# dash-hat.net
KiCad netlist of a schematic drawn in EAGLE
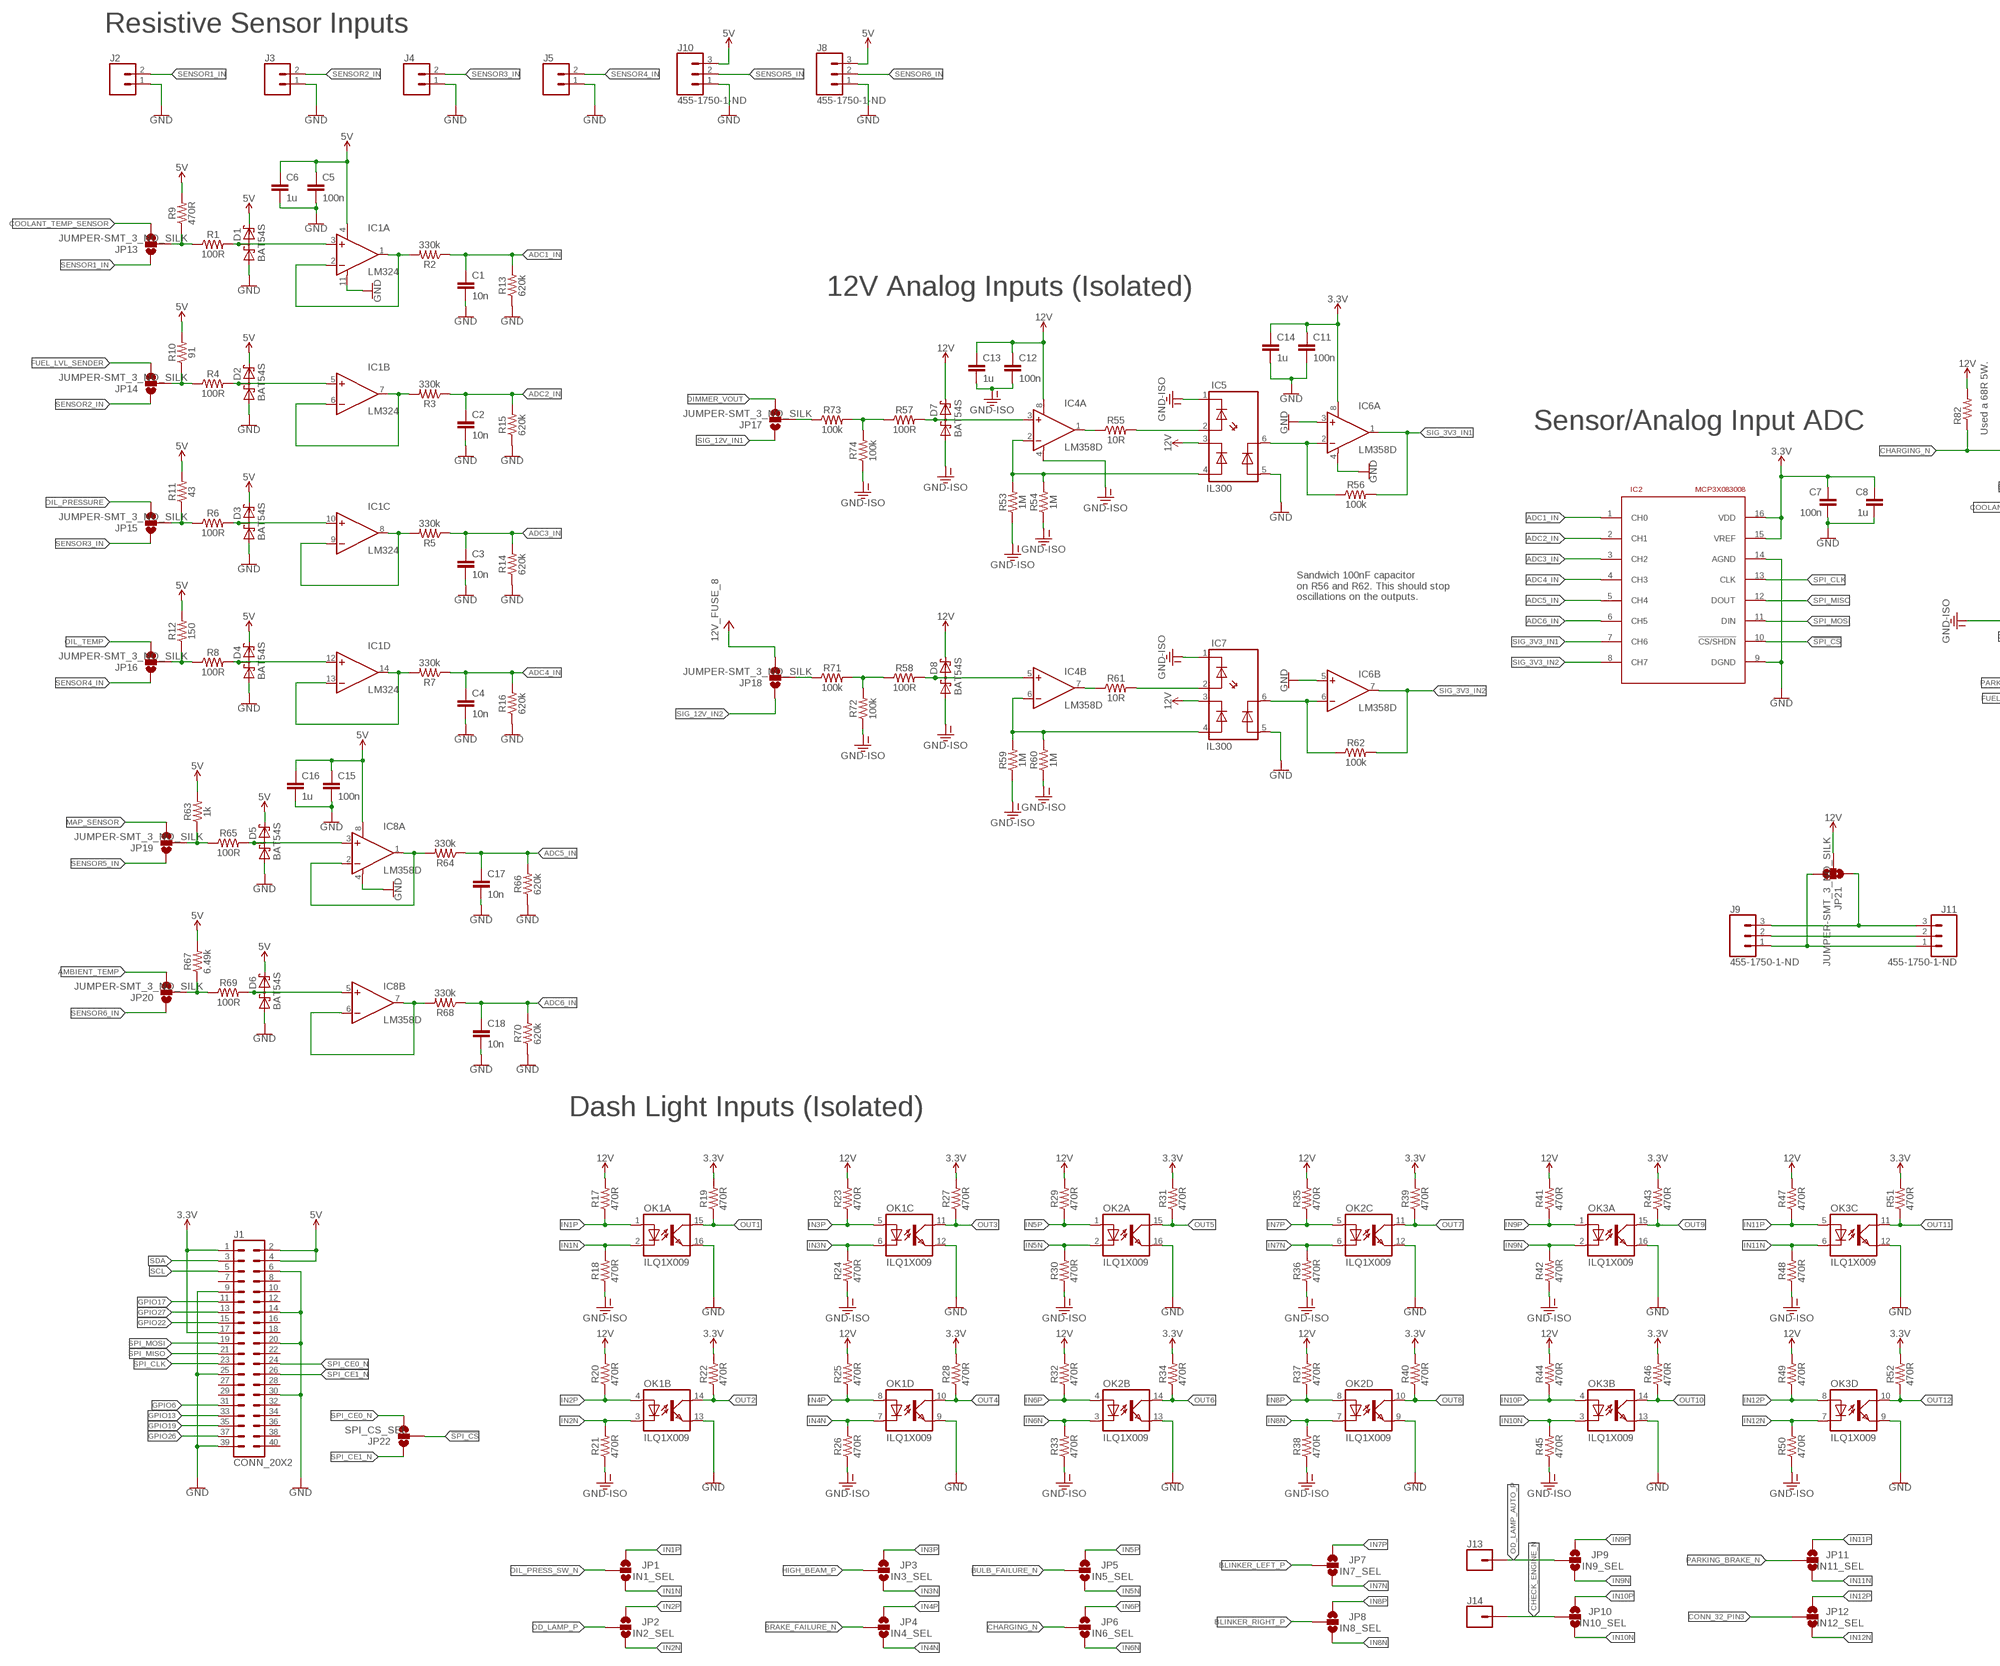
[diagram p0: schematic, sheet 1, part 1 of 2]
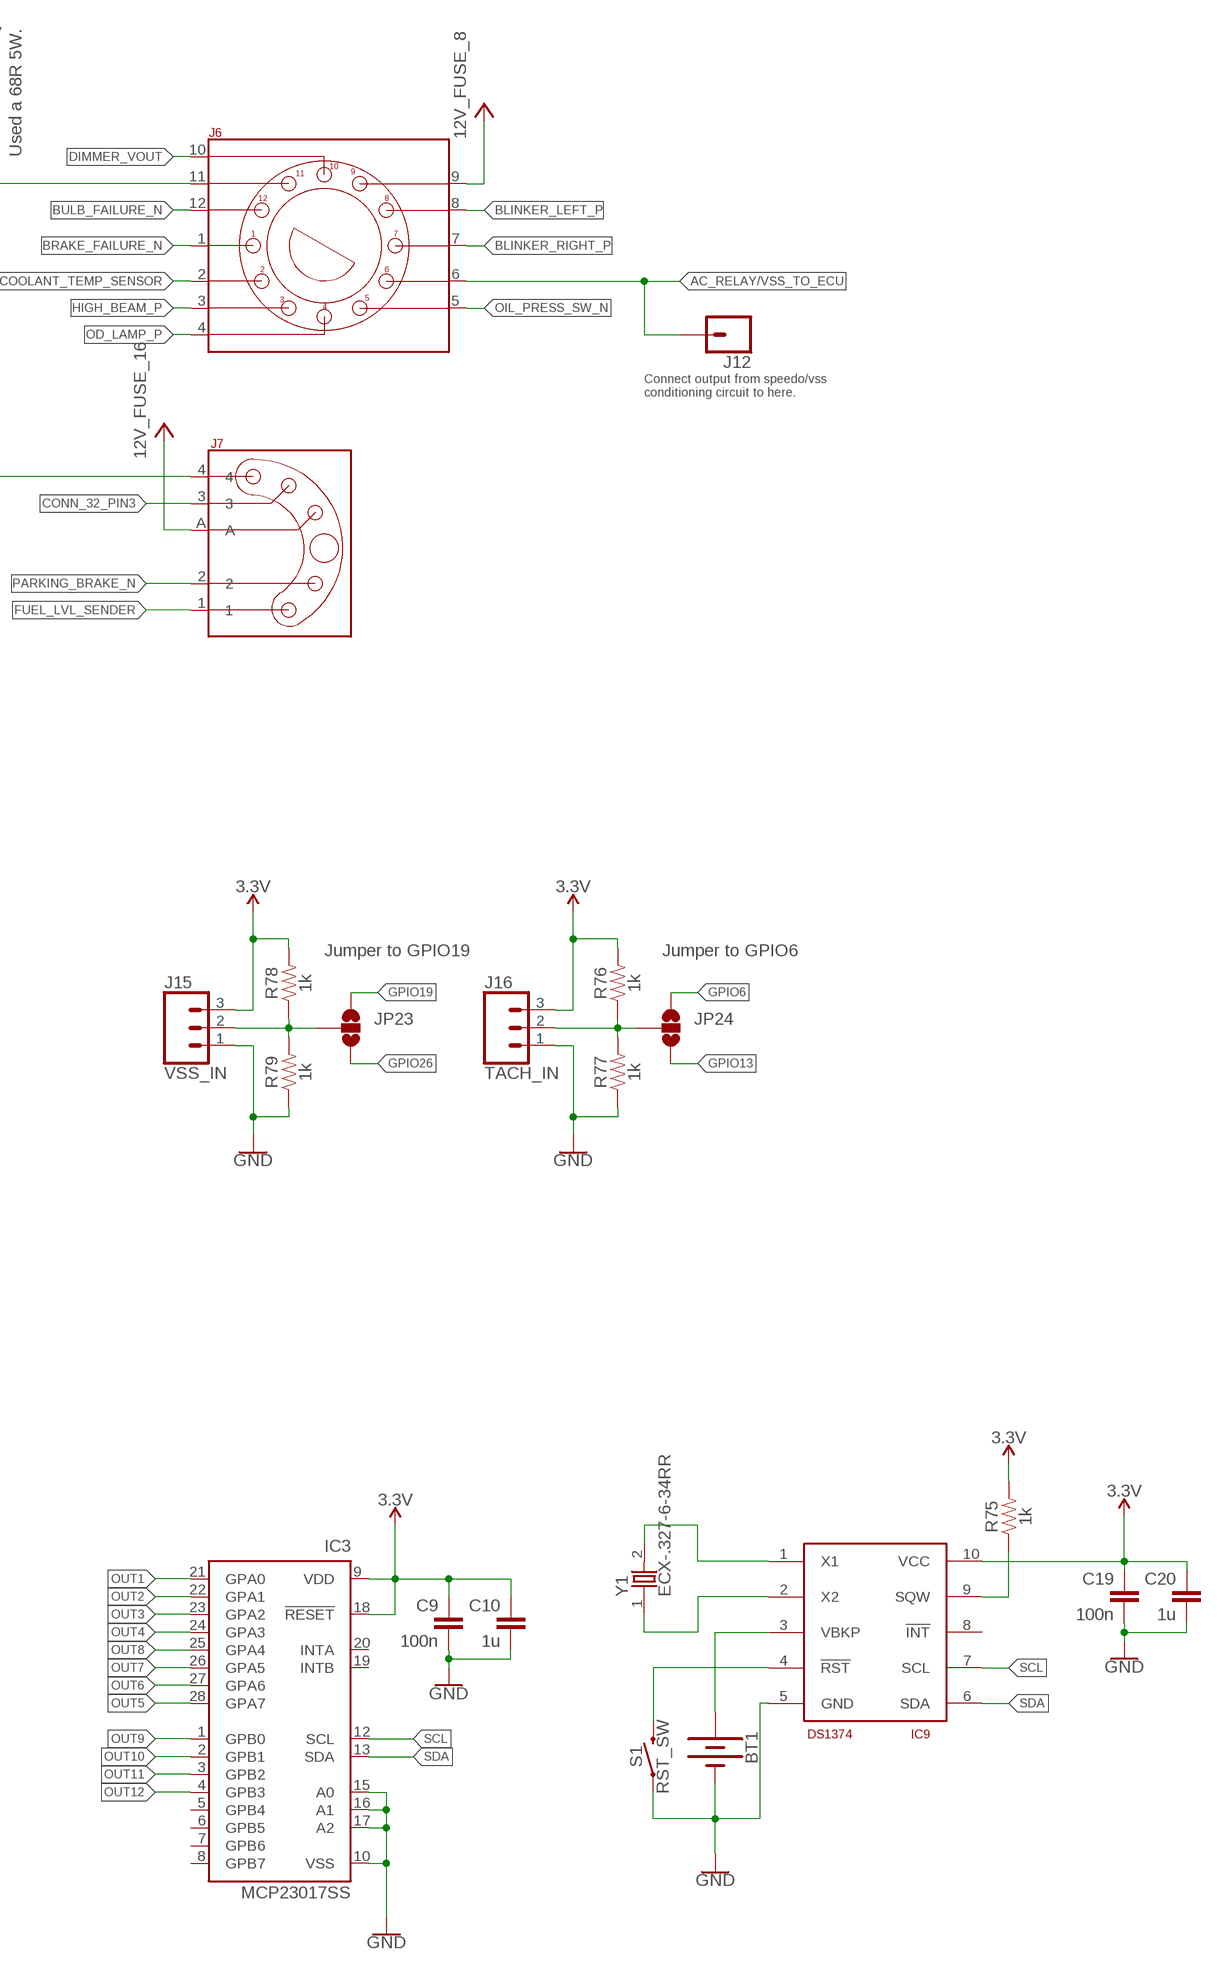
[diagram p1: schematic, sheet 1, part 2 of 2]

(export (version "E")
  (design (tool "Eeschema 10.0.6"))
  (components
    (comp (ref "BT1")
      (value "BATTERY-12MM_SMD")
      (footprint "eagle-import:BATTCON_12MM")
      (libsource (lib "eagle-import") (part "BATTERY-12MM_SMD"))
    )
    (comp (ref "C1")
      (value "10n")
      (footprint "eagle-import:0603")
      (libsource (lib "eagle-import") (part "CL10B103KB8NNNC"))
    )
    (comp (ref "C2")
      (value "10n")
      (footprint "eagle-import:0603")
      (libsource (lib "eagle-import") (part "CL10B103KB8NNNC"))
    )
    (comp (ref "C3")
      (value "10n")
      (footprint "eagle-import:0603")
      (libsource (lib "eagle-import") (part "CL10B103KB8NNNC"))
    )
    (comp (ref "C4")
      (value "10n")
      (footprint "eagle-import:0603")
      (libsource (lib "eagle-import") (part "CL10B103KB8NNNC"))
    )
    (comp (ref "C5")
      (value "100n")
      (footprint "eagle-import:0603")
      (libsource (lib "eagle-import") (part "CL10B104MB8NNNC"))
    )
    (comp (ref "C6")
      (value "1u")
      (footprint "eagle-import:0603")
      (libsource (lib "eagle-import") (part "CL10A105KA8NNNC"))
    )
    (comp (ref "C7")
      (value "100n")
      (footprint "eagle-import:0603")
      (libsource (lib "eagle-import") (part "CL10B104MB8NNNC"))
    )
    (comp (ref "C8")
      (value "1u")
      (footprint "eagle-import:0603")
      (libsource (lib "eagle-import") (part "CL10A105KA8NNNC"))
    )
    (comp (ref "C9")
      (value "100n")
      (footprint "eagle-import:0603")
      (libsource (lib "eagle-import") (part "CL10B104MB8NNNC"))
    )
    (comp (ref "C10")
      (value "1u")
      (footprint "eagle-import:0603")
      (libsource (lib "eagle-import") (part "CL10A105KA8NNNC"))
    )
    (comp (ref "C11")
      (value "100n")
      (footprint "eagle-import:0603")
      (libsource (lib "eagle-import") (part "CL10B104MB8NNNC"))
    )
    (comp (ref "C12")
      (value "100n")
      (footprint "eagle-import:0603")
      (libsource (lib "eagle-import") (part "CL10B104MB8NNNC"))
    )
    (comp (ref "C13")
      (value "1u")
      (footprint "eagle-import:0603")
      (libsource (lib "eagle-import") (part "CL10A105KA8NNNC"))
    )
    (comp (ref "C14")
      (value "1u")
      (footprint "eagle-import:0603")
      (libsource (lib "eagle-import") (part "CL10A105KA8NNNC"))
    )
    (comp (ref "C15")
      (value "100n")
      (footprint "eagle-import:0603")
      (libsource (lib "eagle-import") (part "CL10B104MB8NNNC"))
    )
    (comp (ref "C16")
      (value "1u")
      (footprint "eagle-import:0603")
      (libsource (lib "eagle-import") (part "CL10A105KA8NNNC"))
    )
    (comp (ref "C17")
      (value "10n")
      (footprint "eagle-import:0603")
      (libsource (lib "eagle-import") (part "CL10B103KB8NNNC"))
    )
    (comp (ref "C18")
      (value "10n")
      (footprint "eagle-import:0603")
      (libsource (lib "eagle-import") (part "CL10B103KB8NNNC"))
    )
    (comp (ref "C19")
      (value "100n")
      (footprint "eagle-import:0603")
      (libsource (lib "eagle-import") (part "CL10B104MB8NNNC"))
    )
    (comp (ref "C20")
      (value "1u")
      (footprint "eagle-import:0603")
      (libsource (lib "eagle-import") (part "CL10A105KA8NNNC"))
    )
    (comp (ref "D1")
      (value "BAT54S")
      (footprint "eagle-import:SOT23")
      (libsource (lib "eagle-import") (part "BAT54S"))
    )
    (comp (ref "D2")
      (value "BAT54S")
      (footprint "eagle-import:SOT23")
      (libsource (lib "eagle-import") (part "BAT54S"))
    )
    (comp (ref "D3")
      (value "BAT54S")
      (footprint "eagle-import:SOT23")
      (libsource (lib "eagle-import") (part "BAT54S"))
    )
    (comp (ref "D4")
      (value "BAT54S")
      (footprint "eagle-import:SOT23")
      (libsource (lib "eagle-import") (part "BAT54S"))
    )
    (comp (ref "D5")
      (value "BAT54S")
      (footprint "eagle-import:SOT23")
      (libsource (lib "eagle-import") (part "BAT54S"))
    )
    (comp (ref "D6")
      (value "BAT54S")
      (footprint "eagle-import:SOT23")
      (libsource (lib "eagle-import") (part "BAT54S"))
    )
    (comp (ref "D7")
      (value "BAT54S")
      (footprint "eagle-import:SOT23")
      (libsource (lib "eagle-import") (part "BAT54S"))
    )
    (comp (ref "D8")
      (value "BAT54S")
      (footprint "eagle-import:SOT23")
      (libsource (lib "eagle-import") (part "BAT54S"))
    )
    (comp (ref "IC1")
      (value "LM324")
      (footprint "eagle-import:TSSOP14")
      (libsource (lib "eagle-import") (part "LM324"))
    )
    (comp (ref "IC2")
      (value "MCP3X083008")
      (footprint "eagle-import:SO16")
      (libsource (lib "eagle-import") (part "MCP3X083008"))
    )
    (comp (ref "IC3")
      (value "MCP23017SS")
      (footprint "eagle-import:SSOP28")
      (fields (field (name "MF") "MICROCHIP") (field (name "MPN") "MCP23017-E/SS"))
      (libsource (lib "eagle-import") (part "MCP23017SS"))
    )
    (comp (ref "IC4")
      (value "LM358D")
      (footprint "eagle-import:SO08")
      (libsource (lib "eagle-import") (part "LM358D"))
    )
    (comp (ref "IC5")
      (value "IL300")
      (footprint "eagle-import:DIL8-SMD")
      (libsource (lib "eagle-import") (part "IL300"))
    )
    (comp (ref "IC6")
      (value "LM358D")
      (footprint "eagle-import:SO08")
      (libsource (lib "eagle-import") (part "LM358D"))
    )
    (comp (ref "IC7")
      (value "IL300")
      (footprint "eagle-import:DIL8-SMD")
      (libsource (lib "eagle-import") (part "IL300"))
    )
    (comp (ref "IC8")
      (value "LM358D")
      (footprint "eagle-import:SO08")
      (libsource (lib "eagle-import") (part "LM358D"))
    )
    (comp (ref "IC9")
      (value "DS1374")
      (footprint "eagle-import:UMAX10")
      (libsource (lib "eagle-import") (part "DS1374"))
    )
    (comp (ref "J1")
      (value "CONN_20X2")
      (footprint "eagle-import:2X20")
      (libsource (lib "eagle-import") (part "CONN_20X2"))
    )
    (comp (ref "J2")
      (value "CONN_02")
      (footprint "eagle-import:1X02")
      (libsource (lib "eagle-import") (part "CONN_02"))
    )
    (comp (ref "J3")
      (value "CONN_02")
      (footprint "eagle-import:1X02")
      (libsource (lib "eagle-import") (part "CONN_02"))
    )
    (comp (ref "J4")
      (value "CONN_02")
      (footprint "eagle-import:1X02")
      (libsource (lib "eagle-import") (part "CONN_02"))
    )
    (comp (ref "J5")
      (value "CONN_02")
      (footprint "eagle-import:1X02")
      (libsource (lib "eagle-import") (part "CONN_02"))
    )
    (comp (ref "J6")
      (value "VOLVO_CONN_31")
      (footprint "eagle-import:VOLVO_CON_31")
      (libsource (lib "eagle-import") (part "VOLVO_CONN_31"))
    )
    (comp (ref "J7")
      (value "VOLVO_CONN_32")
      (footprint "eagle-import:VOLVO_CON_32")
      (libsource (lib "eagle-import") (part "VOLVO_CONN_32"))
    )
    (comp (ref "J8")
      (value "455-1750-1-ND")
      (footprint "eagle-import:1X03")
      (libsource (lib "eagle-import") (part "CONN_03"))
    )
    (comp (ref "J9")
      (value "455-1750-1-ND")
      (footprint "eagle-import:1X03")
      (libsource (lib "eagle-import") (part "CONN_03"))
    )
    (comp (ref "J10")
      (value "455-1750-1-ND")
      (footprint "eagle-import:1X03")
      (libsource (lib "eagle-import") (part "CONN_03"))
    )
    (comp (ref "J11")
      (value "455-1750-1-ND")
      (footprint "eagle-import:1X03")
      (libsource (lib "eagle-import") (part "CONN_03"))
    )
    (comp (ref "J12")
      (value "CONN_01OFFSET")
      (footprint "eagle-import:1X01_OFFSET")
      (libsource (lib "eagle-import") (part "CONN_01OFFSET"))
    )
    (comp (ref "J13")
      (value "CONN_01PTH_2MM")
      (footprint "eagle-import:1X01_2MM")
      (libsource (lib "eagle-import") (part "CONN_01PTH_2MM"))
    )
    (comp (ref "J14")
      (value "CONN_01PTH_2MM")
      (footprint "eagle-import:1X01_2MM")
      (libsource (lib "eagle-import") (part "CONN_01PTH_2MM"))
    )
    (comp (ref "J15")
      (value "VSS_IN")
      (footprint "eagle-import:1X03")
      (libsource (lib "eagle-import") (part "CONN_03"))
    )
    (comp (ref "J16")
      (value "TACH_IN")
      (footprint "eagle-import:1X03")
      (libsource (lib "eagle-import") (part "CONN_03"))
    )
    (comp (ref "JP1")
      (value "IN1_SEL")
      (footprint "eagle-import:SMT-JUMPER_3_NO_SILK")
      (libsource (lib "eagle-import") (part "JUMPER-SMT_3_NO_SILK"))
    )
    (comp (ref "JP2")
      (value "IN2_SEL")
      (footprint "eagle-import:SMT-JUMPER_3_NO_SILK")
      (libsource (lib "eagle-import") (part "JUMPER-SMT_3_NO_SILK"))
    )
    (comp (ref "JP3")
      (value "IN3_SEL")
      (footprint "eagle-import:SMT-JUMPER_3_NO_SILK")
      (libsource (lib "eagle-import") (part "JUMPER-SMT_3_NO_SILK"))
    )
    (comp (ref "JP4")
      (value "IN4_SEL")
      (footprint "eagle-import:SMT-JUMPER_3_NO_SILK")
      (libsource (lib "eagle-import") (part "JUMPER-SMT_3_NO_SILK"))
    )
    (comp (ref "JP5")
      (value "IN5_SEL")
      (footprint "eagle-import:SMT-JUMPER_3_NO_SILK")
      (libsource (lib "eagle-import") (part "JUMPER-SMT_3_NO_SILK"))
    )
    (comp (ref "JP6")
      (value "IN6_SEL")
      (footprint "eagle-import:SMT-JUMPER_3_NO_SILK")
      (libsource (lib "eagle-import") (part "JUMPER-SMT_3_NO_SILK"))
    )
    (comp (ref "JP7")
      (value "IN7_SEL")
      (footprint "eagle-import:SMT-JUMPER_3_NO_SILK")
      (libsource (lib "eagle-import") (part "JUMPER-SMT_3_NO_SILK"))
    )
    (comp (ref "JP8")
      (value "IN8_SEL")
      (footprint "eagle-import:SMT-JUMPER_3_NO_SILK")
      (libsource (lib "eagle-import") (part "JUMPER-SMT_3_NO_SILK"))
    )
    (comp (ref "JP9")
      (value "IN9_SEL")
      (footprint "eagle-import:SMT-JUMPER_3_NO_SILK")
      (libsource (lib "eagle-import") (part "JUMPER-SMT_3_NO_SILK"))
    )
    (comp (ref "JP10")
      (value "IN10_SEL")
      (footprint "eagle-import:SMT-JUMPER_3_NO_SILK")
      (libsource (lib "eagle-import") (part "JUMPER-SMT_3_NO_SILK"))
    )
    (comp (ref "JP11")
      (value "IN11_SEL")
      (footprint "eagle-import:SMT-JUMPER_3_NO_SILK")
      (libsource (lib "eagle-import") (part "JUMPER-SMT_3_NO_SILK"))
    )
    (comp (ref "JP12")
      (value "IN12_SEL")
      (footprint "eagle-import:SMT-JUMPER_3_NO_SILK")
      (libsource (lib "eagle-import") (part "JUMPER-SMT_3_NO_SILK"))
    )
    (comp (ref "JP13")
      (value "JUMPER-SMT_3_NO_SILK")
      (footprint "eagle-import:SMT-JUMPER_3_NO_SILK")
      (libsource (lib "eagle-import") (part "JUMPER-SMT_3_NO_SILK"))
    )
    (comp (ref "JP14")
      (value "JUMPER-SMT_3_NO_SILK")
      (footprint "eagle-import:SMT-JUMPER_3_NO_SILK")
      (libsource (lib "eagle-import") (part "JUMPER-SMT_3_NO_SILK"))
    )
    (comp (ref "JP15")
      (value "JUMPER-SMT_3_NO_SILK")
      (footprint "eagle-import:SMT-JUMPER_3_NO_SILK")
      (libsource (lib "eagle-import") (part "JUMPER-SMT_3_NO_SILK"))
    )
    (comp (ref "JP16")
      (value "JUMPER-SMT_3_NO_SILK")
      (footprint "eagle-import:SMT-JUMPER_3_NO_SILK")
      (libsource (lib "eagle-import") (part "JUMPER-SMT_3_NO_SILK"))
    )
    (comp (ref "JP17")
      (value "JUMPER-SMT_3_NO_SILK")
      (footprint "eagle-import:SMT-JUMPER_3_NO_SILK")
      (libsource (lib "eagle-import") (part "JUMPER-SMT_3_NO_SILK"))
    )
    (comp (ref "JP18")
      (value "JUMPER-SMT_3_NO_SILK")
      (footprint "eagle-import:SMT-JUMPER_3_NO_SILK")
      (libsource (lib "eagle-import") (part "JUMPER-SMT_3_NO_SILK"))
    )
    (comp (ref "JP19")
      (value "JUMPER-SMT_3_NO_SILK")
      (footprint "eagle-import:SMT-JUMPER_3_NO_SILK")
      (libsource (lib "eagle-import") (part "JUMPER-SMT_3_NO_SILK"))
    )
    (comp (ref "JP20")
      (value "JUMPER-SMT_3_NO_SILK")
      (footprint "eagle-import:SMT-JUMPER_3_NO_SILK")
      (libsource (lib "eagle-import") (part "JUMPER-SMT_3_NO_SILK"))
    )
    (comp (ref "JP21")
      (value "JUMPER-SMT_3_NO_SILK")
      (footprint "eagle-import:SMT-JUMPER_3_NO_SILK")
      (libsource (lib "eagle-import") (part "JUMPER-SMT_3_NO_SILK"))
    )
    (comp (ref "JP22")
      (value "SPI_CS_SEL")
      (footprint "eagle-import:SMT-JUMPER_3_NO_SILK")
      (libsource (lib "eagle-import") (part "JUMPER-SMT_3_NO_SILK"))
    )
    (comp (ref "JP23")
      (value "TACH_INPUT_SEL")
      (footprint "eagle-import:SMT-JUMPER_3_NO_SILK")
      (libsource (lib "eagle-import") (part "JUMPER-SMT_3_NO_SILK"))
    )
    (comp (ref "JP24")
      (value "TACH_INPUT_SEL")
      (footprint "eagle-import:SMT-JUMPER_3_NO_SILK")
      (libsource (lib "eagle-import") (part "JUMPER-SMT_3_NO_SILK"))
    )
    (comp (ref "OK1")
      (value "ILQ1X009")
      (footprint "eagle-import:SMD16")
      (libsource (lib "eagle-import") (part "ILQ1X009"))
    )
    (comp (ref "OK2")
      (value "ILQ1X009")
      (footprint "eagle-import:SMD16")
      (libsource (lib "eagle-import") (part "ILQ1X009"))
    )
    (comp (ref "OK3")
      (value "ILQ1X009")
      (footprint "eagle-import:SMD16")
      (libsource (lib "eagle-import") (part "ILQ1X009"))
    )
    (comp (ref "R1")
      (value "100R")
      (footprint "eagle-import:0603")
      (libsource (lib "eagle-import") (part "RC0603JR-07100RL"))
    )
    (comp (ref "R2")
      (value "330k")
      (footprint "eagle-import:0603")
      (libsource (lib "eagle-import") (part "RC0603JR-07330KL"))
    )
    (comp (ref "R3")
      (value "330k")
      (footprint "eagle-import:0603")
      (libsource (lib "eagle-import") (part "RC0603JR-07330KL"))
    )
    (comp (ref "R4")
      (value "100R")
      (footprint "eagle-import:0603")
      (libsource (lib "eagle-import") (part "RC0603JR-07100RL"))
    )
    (comp (ref "R5")
      (value "330k")
      (footprint "eagle-import:0603")
      (libsource (lib "eagle-import") (part "RC0603JR-07330KL"))
    )
    (comp (ref "R6")
      (value "100R")
      (footprint "eagle-import:0603")
      (libsource (lib "eagle-import") (part "RC0603JR-07100RL"))
    )
    (comp (ref "R7")
      (value "330k")
      (footprint "eagle-import:0603")
      (libsource (lib "eagle-import") (part "RC0603JR-07330KL"))
    )
    (comp (ref "R8")
      (value "100R")
      (footprint "eagle-import:0603")
      (libsource (lib "eagle-import") (part "RC0603JR-07100RL"))
    )
    (comp (ref "R9")
      (value "470R")
      (footprint "eagle-import:0603")
      (libsource (lib "eagle-import") (part "RC0603JR-07470RL"))
    )
    (comp (ref "R10")
      (value "91")
      (footprint "eagle-import:0603")
      (libsource (lib "eagle-import") (part "RC0603JR-071KL"))
    )
    (comp (ref "R11")
      (value "43")
      (footprint "eagle-import:0603")
      (libsource (lib "eagle-import") (part "RC0603JR-071KL"))
    )
    (comp (ref "R12")
      (value "150")
      (footprint "eagle-import:0603")
      (libsource (lib "eagle-import") (part "RC0603JR-071KL"))
    )
    (comp (ref "R13")
      (value "620k")
      (footprint "eagle-import:0603")
      (libsource (lib "eagle-import") (part "RC0603JR-07620KL"))
    )
    (comp (ref "R14")
      (value "620k")
      (footprint "eagle-import:0603")
      (libsource (lib "eagle-import") (part "RC0603JR-07620KL"))
    )
    (comp (ref "R15")
      (value "620k")
      (footprint "eagle-import:0603")
      (libsource (lib "eagle-import") (part "RC0603JR-07620KL"))
    )
    (comp (ref "R16")
      (value "620k")
      (footprint "eagle-import:0603")
      (libsource (lib "eagle-import") (part "RC0603JR-07620KL"))
    )
    (comp (ref "R17")
      (value "470R")
      (footprint "eagle-import:0603")
      (libsource (lib "eagle-import") (part "RC0603JR-07470RL"))
    )
    (comp (ref "R18")
      (value "470R")
      (footprint "eagle-import:0603")
      (libsource (lib "eagle-import") (part "RC0603JR-07470RL"))
    )
    (comp (ref "R19")
      (value "470R")
      (footprint "eagle-import:0603")
      (libsource (lib "eagle-import") (part "RC0603JR-07470RL"))
    )
    (comp (ref "R20")
      (value "470R")
      (footprint "eagle-import:0603")
      (libsource (lib "eagle-import") (part "RC0603JR-07470RL"))
    )
    (comp (ref "R21")
      (value "470R")
      (footprint "eagle-import:0603")
      (libsource (lib "eagle-import") (part "RC0603JR-07470RL"))
    )
    (comp (ref "R22")
      (value "470R")
      (footprint "eagle-import:0603")
      (libsource (lib "eagle-import") (part "RC0603JR-07470RL"))
    )
    (comp (ref "R23")
      (value "470R")
      (footprint "eagle-import:0603")
      (libsource (lib "eagle-import") (part "RC0603JR-07470RL"))
    )
    (comp (ref "R24")
      (value "470R")
      (footprint "eagle-import:0603")
      (libsource (lib "eagle-import") (part "RC0603JR-07470RL"))
    )
    (comp (ref "R25")
      (value "470R")
      (footprint "eagle-import:0603")
      (libsource (lib "eagle-import") (part "RC0603JR-07470RL"))
    )
    (comp (ref "R26")
      (value "470R")
      (footprint "eagle-import:0603")
      (libsource (lib "eagle-import") (part "RC0603JR-07470RL"))
    )
    (comp (ref "R27")
      (value "470R")
      (footprint "eagle-import:0603")
      (libsource (lib "eagle-import") (part "RC0603JR-07470RL"))
    )
    (comp (ref "R28")
      (value "470R")
      (footprint "eagle-import:0603")
      (libsource (lib "eagle-import") (part "RC0603JR-07470RL"))
    )
    (comp (ref "R29")
      (value "470R")
      (footprint "eagle-import:0603")
      (libsource (lib "eagle-import") (part "RC0603JR-07470RL"))
    )
    (comp (ref "R30")
      (value "470R")
      (footprint "eagle-import:0603")
      (libsource (lib "eagle-import") (part "RC0603JR-07470RL"))
    )
    (comp (ref "R31")
      (value "470R")
      (footprint "eagle-import:0603")
      (libsource (lib "eagle-import") (part "RC0603JR-07470RL"))
    )
    (comp (ref "R32")
      (value "470R")
      (footprint "eagle-import:0603")
      (libsource (lib "eagle-import") (part "RC0603JR-07470RL"))
    )
    (comp (ref "R33")
      (value "470R")
      (footprint "eagle-import:0603")
      (libsource (lib "eagle-import") (part "RC0603JR-07470RL"))
    )
    (comp (ref "R34")
      (value "470R")
      (footprint "eagle-import:0603")
      (libsource (lib "eagle-import") (part "RC0603JR-07470RL"))
    )
    (comp (ref "R35")
      (value "470R")
      (footprint "eagle-import:0603")
      (libsource (lib "eagle-import") (part "RC0603JR-07470RL"))
    )
    (comp (ref "R36")
      (value "470R")
      (footprint "eagle-import:0603")
      (libsource (lib "eagle-import") (part "RC0603JR-07470RL"))
    )
    (comp (ref "R37")
      (value "470R")
      (footprint "eagle-import:0603")
      (libsource (lib "eagle-import") (part "RC0603JR-07470RL"))
    )
    (comp (ref "R38")
      (value "470R")
      (footprint "eagle-import:0603")
      (libsource (lib "eagle-import") (part "RC0603JR-07470RL"))
    )
    (comp (ref "R39")
      (value "470R")
      (footprint "eagle-import:0603")
      (libsource (lib "eagle-import") (part "RC0603JR-07470RL"))
    )
    (comp (ref "R40")
      (value "470R")
      (footprint "eagle-import:0603")
      (libsource (lib "eagle-import") (part "RC0603JR-07470RL"))
    )
    (comp (ref "R41")
      (value "470R")
      (footprint "eagle-import:0603")
      (libsource (lib "eagle-import") (part "RC0603JR-07470RL"))
    )
    (comp (ref "R42")
      (value "470R")
      (footprint "eagle-import:0603")
      (libsource (lib "eagle-import") (part "RC0603JR-07470RL"))
    )
    (comp (ref "R43")
      (value "470R")
      (footprint "eagle-import:0603")
      (libsource (lib "eagle-import") (part "RC0603JR-07470RL"))
    )
    (comp (ref "R44")
      (value "470R")
      (footprint "eagle-import:0603")
      (libsource (lib "eagle-import") (part "RC0603JR-07470RL"))
    )
    (comp (ref "R45")
      (value "470R")
      (footprint "eagle-import:0603")
      (libsource (lib "eagle-import") (part "RC0603JR-07470RL"))
    )
    (comp (ref "R46")
      (value "470R")
      (footprint "eagle-import:0603")
      (libsource (lib "eagle-import") (part "RC0603JR-07470RL"))
    )
    (comp (ref "R47")
      (value "470R")
      (footprint "eagle-import:0603")
      (libsource (lib "eagle-import") (part "RC0603JR-07470RL"))
    )
    (comp (ref "R48")
      (value "470R")
      (footprint "eagle-import:0603")
      (libsource (lib "eagle-import") (part "RC0603JR-07470RL"))
    )
    (comp (ref "R49")
      (value "470R")
      (footprint "eagle-import:0603")
      (libsource (lib "eagle-import") (part "RC0603JR-07470RL"))
    )
    (comp (ref "R50")
      (value "470R")
      (footprint "eagle-import:0603")
      (libsource (lib "eagle-import") (part "RC0603JR-07470RL"))
    )
    (comp (ref "R51")
      (value "470R")
      (footprint "eagle-import:0603")
      (libsource (lib "eagle-import") (part "RC0603JR-07470RL"))
    )
    (comp (ref "R52")
      (value "470R")
      (footprint "eagle-import:0603")
      (libsource (lib "eagle-import") (part "RC0603JR-07470RL"))
    )
    (comp (ref "R53")
      (value "1M")
      (footprint "eagle-import:0603")
      (libsource (lib "eagle-import") (part "RC0603JR-071ML"))
    )
    (comp (ref "R54")
      (value "1M")
      (footprint "eagle-import:0603")
      (libsource (lib "eagle-import") (part "RC0603JR-071ML"))
    )
    (comp (ref "R55")
      (value "10R")
      (footprint "eagle-import:0603")
      (libsource (lib "eagle-import") (part "RC0603JR-1310RL"))
    )
    (comp (ref "R56")
      (value "100k")
      (footprint "eagle-import:0603")
      (libsource (lib "eagle-import") (part "RC0603JR-07100KL"))
    )
    (comp (ref "R57")
      (value "100R")
      (footprint "eagle-import:0603")
      (libsource (lib "eagle-import") (part "RC0603JR-07100RL"))
    )
    (comp (ref "R58")
      (value "100R")
      (footprint "eagle-import:0603")
      (libsource (lib "eagle-import") (part "RC0603JR-07100RL"))
    )
    (comp (ref "R59")
      (value "1M")
      (footprint "eagle-import:0603")
      (libsource (lib "eagle-import") (part "RC0603JR-071ML"))
    )
    (comp (ref "R60")
      (value "1M")
      (footprint "eagle-import:0603")
      (libsource (lib "eagle-import") (part "RC0603JR-071ML"))
    )
    (comp (ref "R61")
      (value "10R")
      (footprint "eagle-import:0603")
      (libsource (lib "eagle-import") (part "RC0603JR-1310RL"))
    )
    (comp (ref "R62")
      (value "100k")
      (footprint "eagle-import:0603")
      (libsource (lib "eagle-import") (part "RC0603JR-07100KL"))
    )
    (comp (ref "R63")
      (value "1k")
      (footprint "eagle-import:0603")
      (libsource (lib "eagle-import") (part "RC0603JR-071KL"))
    )
    (comp (ref "R64")
      (value "330k")
      (footprint "eagle-import:0603")
      (libsource (lib "eagle-import") (part "RC0603JR-07330KL"))
    )
    (comp (ref "R65")
      (value "100R")
      (footprint "eagle-import:0603")
      (libsource (lib "eagle-import") (part "RC0603JR-07100RL"))
    )
    (comp (ref "R66")
      (value "620k")
      (footprint "eagle-import:0603")
      (libsource (lib "eagle-import") (part "RC0603JR-07620KL"))
    )
    (comp (ref "R67")
      (value "6.49k")
      (footprint "eagle-import:0603")
      (libsource (lib "eagle-import") (part "RC0603JR-071KL"))
    )
    (comp (ref "R68")
      (value "330k")
      (footprint "eagle-import:0603")
      (libsource (lib "eagle-import") (part "RC0603JR-07330KL"))
    )
    (comp (ref "R69")
      (value "100R")
      (footprint "eagle-import:0603")
      (libsource (lib "eagle-import") (part "RC0603JR-07100RL"))
    )
    (comp (ref "R70")
      (value "620k")
      (footprint "eagle-import:0603")
      (libsource (lib "eagle-import") (part "RC0603JR-07620KL"))
    )
    (comp (ref "R71")
      (value "100k")
      (footprint "eagle-import:0603")
      (libsource (lib "eagle-import") (part "RC0603JR-07100KL"))
    )
    (comp (ref "R72")
      (value "100k")
      (footprint "eagle-import:0603")
      (libsource (lib "eagle-import") (part "RC0603JR-07100KL"))
    )
    (comp (ref "R73")
      (value "100k")
      (footprint "eagle-import:0603")
      (libsource (lib "eagle-import") (part "RC0603JR-07100KL"))
    )
    (comp (ref "R74")
      (value "100k")
      (footprint "eagle-import:0603")
      (libsource (lib "eagle-import") (part "RC0603JR-07100KL"))
    )
    (comp (ref "R75")
      (value "1k")
      (footprint "eagle-import:0603")
      (libsource (lib "eagle-import") (part "RC0603JR-071KL"))
    )
    (comp (ref "R76")
      (value "1k")
      (footprint "eagle-import:0603")
      (libsource (lib "eagle-import") (part "RC0603JR-071KL"))
    )
    (comp (ref "R77")
      (value "1k")
      (footprint "eagle-import:0603")
      (libsource (lib "eagle-import") (part "RC0603JR-071KL"))
    )
    (comp (ref "R78")
      (value "1k")
      (footprint "eagle-import:0603")
      (libsource (lib "eagle-import") (part "RC0603JR-071KL"))
    )
    (comp (ref "R79")
      (value "1k")
      (footprint "eagle-import:0603")
      (libsource (lib "eagle-import") (part "RC0603JR-071KL"))
    )
    (comp (ref "R82")
      (value "R-US_0617/17")
      (footprint "eagle-import:0617_17")
      (libsource (lib "eagle-import") (part "R-US_0617/17"))
    )
    (comp (ref "S1")
      (value "RST_SW")
      (footprint "eagle-import:TACTILE_SWITCH_SMD_6.0X3.5MM")
      (libsource (lib "eagle-import") (part "MOMENTARY-SWITCH-SPST-SMD-6.0X3.5MM"))
    )
    (comp (ref "Y1")
      (value "ECX-.327-6-34RR")
      (footprint "eagle-import:ECX-34RR")
      (libsource (lib "eagle-import") (part "ECX-.327-6-34RR"))
    )
  )
  (nets
    (net (code "1") (name "/~{SPI_CS}") (class "Default")
      (node (ref "IC2") (pin "10") (pinfunction "~{CS/SHDN}_10") (pintype "bidirectional"))
      (node (ref "JP22") (pin "2") (pinfunction "2_2") (pintype "passive"))
    )
    (net (code "2") (name "3.3V") (class "Default")
      (node (ref "C10") (pin "1") (pinfunction "1_1") (pintype "passive"))
      (node (ref "C11") (pin "1") (pinfunction "1_1") (pintype "passive"))
      (node (ref "C14") (pin "1") (pinfunction "1_1") (pintype "passive"))
      (node (ref "C19") (pin "1") (pinfunction "1_1") (pintype "passive"))
      (node (ref "C20") (pin "1") (pinfunction "1_1") (pintype "passive"))
      (node (ref "C7") (pin "1") (pinfunction "1_1") (pintype "passive"))
      (node (ref "C8") (pin "1") (pinfunction "1_1") (pintype "passive"))
      (node (ref "C9") (pin "1") (pinfunction "1_1") (pintype "passive"))
      (node (ref "IC2") (pin "15") (pinfunction "VREF_15") (pintype "bidirectional"))
      (node (ref "IC2") (pin "16") (pinfunction "VDD_16") (pintype "bidirectional"))
      (node (ref "IC3") (pin "18") (pinfunction "~{RESET}_18") (pintype "input"))
      (node (ref "IC3") (pin "9") (pinfunction "VDD_9") (pintype "power_in"))
      (node (ref "IC6") (pin "8") (pinfunction "V+_8") (pintype "power_in"))
      (node (ref "IC9") (pin "10") (pinfunction "VCC_10") (pintype "power_in"))
      (node (ref "J1") (pin "1") (pinfunction "1_1") (pintype "passive"))
      (node (ref "J1") (pin "17") (pinfunction "17_17") (pintype "passive"))
      (node (ref "J15") (pin "3") (pinfunction "3_3") (pintype "passive"))
      (node (ref "J16") (pin "3") (pinfunction "3_3") (pintype "passive"))
      (node (ref "R19") (pin "2") (pinfunction "2_2") (pintype "passive"))
      (node (ref "R22") (pin "2") (pinfunction "2_2") (pintype "passive"))
      (node (ref "R27") (pin "2") (pinfunction "2_2") (pintype "passive"))
      (node (ref "R28") (pin "2") (pinfunction "2_2") (pintype "passive"))
      (node (ref "R31") (pin "2") (pinfunction "2_2") (pintype "passive"))
      (node (ref "R34") (pin "2") (pinfunction "2_2") (pintype "passive"))
      (node (ref "R39") (pin "2") (pinfunction "2_2") (pintype "passive"))
      (node (ref "R40") (pin "2") (pinfunction "2_2") (pintype "passive"))
      (node (ref "R43") (pin "2") (pinfunction "2_2") (pintype "passive"))
      (node (ref "R46") (pin "2") (pinfunction "2_2") (pintype "passive"))
      (node (ref "R51") (pin "2") (pinfunction "2_2") (pintype "passive"))
      (node (ref "R52") (pin "2") (pinfunction "2_2") (pintype "passive"))
      (node (ref "R75") (pin "2") (pinfunction "2_2") (pintype "passive"))
      (node (ref "R76") (pin "2") (pinfunction "2_2") (pintype "passive"))
      (node (ref "R78") (pin "2") (pinfunction "2_2") (pintype "passive"))
    )
    (net (code "3") (name "5V") (class "Default")
      (node (ref "C15") (pin "1") (pinfunction "1_1") (pintype "passive"))
      (node (ref "C16") (pin "1") (pinfunction "1_1") (pintype "passive"))
      (node (ref "C5") (pin "1") (pinfunction "1_1") (pintype "passive"))
      (node (ref "C6") (pin "1") (pinfunction "1_1") (pintype "passive"))
      (node (ref "D1") (pin "2") (pinfunction "C2_2") (pintype "passive"))
      (node (ref "D2") (pin "2") (pinfunction "C2_2") (pintype "passive"))
      (node (ref "D3") (pin "2") (pinfunction "C2_2") (pintype "passive"))
      (node (ref "D4") (pin "2") (pinfunction "C2_2") (pintype "passive"))
      (node (ref "D5") (pin "2") (pinfunction "C2_2") (pintype "passive"))
      (node (ref "D6") (pin "2") (pinfunction "C2_2") (pintype "passive"))
      (node (ref "IC1") (pin "4") (pinfunction "V+_4") (pintype "power_in"))
      (node (ref "IC8") (pin "8") (pinfunction "V+_8") (pintype "power_in"))
      (node (ref "J1") (pin "2") (pinfunction "2_2") (pintype "passive"))
      (node (ref "J1") (pin "4") (pinfunction "4_4") (pintype "passive"))
      (node (ref "J10") (pin "3") (pinfunction "3_3") (pintype "passive"))
      (node (ref "J8") (pin "3") (pinfunction "3_3") (pintype "passive"))
      (node (ref "R10") (pin "2") (pinfunction "2_2") (pintype "passive"))
      (node (ref "R11") (pin "2") (pinfunction "2_2") (pintype "passive"))
      (node (ref "R12") (pin "2") (pinfunction "2_2") (pintype "passive"))
      (node (ref "R63") (pin "2") (pinfunction "2_2") (pintype "passive"))
      (node (ref "R67") (pin "2") (pinfunction "2_2") (pintype "passive"))
      (node (ref "R9") (pin "2") (pinfunction "2_2") (pintype "passive"))
    )
    (net (code "4") (name "12V") (class "Default")
      (node (ref "C12") (pin "1") (pinfunction "1_1") (pintype "passive"))
      (node (ref "C13") (pin "1") (pinfunction "1_1") (pintype "passive"))
      (node (ref "D7") (pin "2") (pinfunction "C2_2") (pintype "passive"))
      (node (ref "D8") (pin "2") (pinfunction "C2_2") (pintype "passive"))
      (node (ref "IC4") (pin "8") (pinfunction "V+_8") (pintype "power_in"))
      (node (ref "IC5") (pin "3") (pinfunction "C3_3") (pintype "passive"))
      (node (ref "IC7") (pin "3") (pinfunction "C3_3") (pintype "passive"))
      (node (ref "JP21") (pin "2") (pinfunction "2_2") (pintype "passive"))
      (node (ref "R17") (pin "2") (pinfunction "2_2") (pintype "passive"))
      (node (ref "R20") (pin "2") (pinfunction "2_2") (pintype "passive"))
      (node (ref "R23") (pin "2") (pinfunction "2_2") (pintype "passive"))
      (node (ref "R25") (pin "2") (pinfunction "2_2") (pintype "passive"))
      (node (ref "R29") (pin "2") (pinfunction "2_2") (pintype "passive"))
      (node (ref "R32") (pin "2") (pinfunction "2_2") (pintype "passive"))
      (node (ref "R35") (pin "2") (pinfunction "2_2") (pintype "passive"))
      (node (ref "R37") (pin "2") (pinfunction "2_2") (pintype "passive"))
      (node (ref "R41") (pin "2") (pinfunction "2_2") (pintype "passive"))
      (node (ref "R44") (pin "2") (pinfunction "2_2") (pintype "passive"))
      (node (ref "R47") (pin "2") (pinfunction "2_2") (pintype "passive"))
      (node (ref "R49") (pin "2") (pinfunction "2_2") (pintype "passive"))
      (node (ref "R82") (pin "2") (pinfunction "2_2") (pintype "passive"))
    )
    (net (code "5") (name "12V_FUSE_8") (class "Default")
      (node (ref "J6") (pin "9") (pinfunction "9_9") (pintype "bidirectional"))
      (node (ref "JP18") (pin "3") (pinfunction "3_3") (pintype "passive"))
    )
    (net (code "6") (name "12V_FUSE_16") (class "Default")
      (node (ref "J7") (pin "A") (pinfunction "A_A") (pintype "bidirectional"))
    )
    (net (code "7") (name "AC_RELAY{slash}VSS_TO_ECU") (class "Default")
      (node (ref "J12") (pin "1") (pinfunction "1_1") (pintype "passive"))
      (node (ref "J6") (pin "6") (pinfunction "6_6") (pintype "bidirectional"))
    )
    (net (code "8") (name "ADC1_IN") (class "Default")
      (node (ref "C1") (pin "1") (pinfunction "1_1") (pintype "passive"))
      (node (ref "IC2") (pin "1") (pinfunction "CH0_1") (pintype "bidirectional"))
      (node (ref "R13") (pin "2") (pinfunction "2_2") (pintype "passive"))
      (node (ref "R2") (pin "1") (pinfunction "1_1") (pintype "passive"))
    )
    (net (code "9") (name "ADC2_IN") (class "Default")
      (node (ref "C2") (pin "1") (pinfunction "1_1") (pintype "passive"))
      (node (ref "IC2") (pin "2") (pinfunction "CH1_2") (pintype "bidirectional"))
      (node (ref "R15") (pin "2") (pinfunction "2_2") (pintype "passive"))
      (node (ref "R3") (pin "1") (pinfunction "1_1") (pintype "passive"))
    )
    (net (code "10") (name "ADC3_IN") (class "Default")
      (node (ref "C3") (pin "1") (pinfunction "1_1") (pintype "passive"))
      (node (ref "IC2") (pin "3") (pinfunction "CH2_3") (pintype "bidirectional"))
      (node (ref "R14") (pin "2") (pinfunction "2_2") (pintype "passive"))
      (node (ref "R5") (pin "1") (pinfunction "1_1") (pintype "passive"))
    )
    (net (code "11") (name "ADC4_IN") (class "Default")
      (node (ref "C4") (pin "1") (pinfunction "1_1") (pintype "passive"))
      (node (ref "IC2") (pin "4") (pinfunction "CH3_4") (pintype "bidirectional"))
      (node (ref "R16") (pin "2") (pinfunction "2_2") (pintype "passive"))
      (node (ref "R7") (pin "1") (pinfunction "1_1") (pintype "passive"))
    )
    (net (code "12") (name "ADC5_IN") (class "Default")
      (node (ref "C17") (pin "1") (pinfunction "1_1") (pintype "passive"))
      (node (ref "IC2") (pin "5") (pinfunction "CH4_5") (pintype "bidirectional"))
      (node (ref "R64") (pin "1") (pinfunction "1_1") (pintype "passive"))
      (node (ref "R66") (pin "2") (pinfunction "2_2") (pintype "passive"))
    )
    (net (code "13") (name "ADC6_IN") (class "Default")
      (node (ref "C18") (pin "1") (pinfunction "1_1") (pintype "passive"))
      (node (ref "IC2") (pin "6") (pinfunction "CH5_6") (pintype "bidirectional"))
      (node (ref "R68") (pin "1") (pinfunction "1_1") (pintype "passive"))
      (node (ref "R70") (pin "2") (pinfunction "2_2") (pintype "passive"))
    )
    (net (code "14") (name "AMBIENT_TEMP") (class "Default")
      (node (ref "JP20") (pin "3") (pinfunction "3_3") (pintype "passive"))
    )
    (net (code "15") (name "BLINKER_LEFT_P") (class "Default")
      (node (ref "J6") (pin "8") (pinfunction "8_8") (pintype "bidirectional"))
      (node (ref "JP7") (pin "2") (pinfunction "2_2") (pintype "passive"))
    )
    (net (code "16") (name "BLINKER_RIGHT_P") (class "Default")
      (node (ref "J6") (pin "7") (pinfunction "7_7") (pintype "bidirectional"))
      (node (ref "JP8") (pin "2") (pinfunction "2_2") (pintype "passive"))
    )
    (net (code "17") (name "BRAKE_FAILURE_N") (class "Default")
      (node (ref "J6") (pin "1") (pinfunction "1_1") (pintype "bidirectional"))
      (node (ref "JP4") (pin "2") (pinfunction "2_2") (pintype "passive"))
    )
    (net (code "18") (name "BULB_FAILURE_N") (class "Default")
      (node (ref "J6") (pin "12") (pinfunction "12_12") (pintype "bidirectional"))
      (node (ref "JP5") (pin "2") (pinfunction "2_2") (pintype "passive"))
    )
    (net (code "19") (name "CHARGING_N") (class "Default")
      (node (ref "J6") (pin "11") (pinfunction "11_11") (pintype "bidirectional"))
      (node (ref "JP6") (pin "2") (pinfunction "2_2") (pintype "passive"))
      (node (ref "R82") (pin "1") (pinfunction "1_1") (pintype "passive"))
    )
    (net (code "20") (name "CHECK_ENGINE_N") (class "Default")
      (node (ref "J14") (pin "1") (pinfunction "1_1") (pintype "passive"))
      (node (ref "JP10") (pin "2") (pinfunction "2_2") (pintype "passive"))
    )
    (net (code "21") (name "CONN_32_PIN3") (class "Default")
      (node (ref "J7") (pin "3") (pinfunction "3_3") (pintype "bidirectional"))
      (node (ref "JP12") (pin "2") (pinfunction "2_2") (pintype "passive"))
    )
    (net (code "22") (name "COOLANT_TEMP_SENSOR") (class "Default")
      (node (ref "J6") (pin "2") (pinfunction "2_2") (pintype "bidirectional"))
      (node (ref "JP13") (pin "3") (pinfunction "3_3") (pintype "passive"))
    )
    (net (code "23") (name "DIMMER_VOUT") (class "Default")
      (node (ref "J6") (pin "10") (pinfunction "10_10") (pintype "bidirectional"))
      (node (ref "JP17") (pin "3") (pinfunction "3_3") (pintype "passive"))
    )
    (net (code "24") (name "FUEL_LVL_SENDER") (class "Default")
      (node (ref "J7") (pin "1") (pinfunction "1_1") (pintype "bidirectional"))
      (node (ref "JP14") (pin "3") (pinfunction "3_3") (pintype "passive"))
    )
    (net (code "25") (name "GND") (class "Default")
      (node (ref "BT1") (pin "GND") (pinfunction "-_GND") (pintype "power_in"))
      (node (ref "C1") (pin "2") (pinfunction "2_2") (pintype "passive"))
      (node (ref "C10") (pin "2") (pinfunction "2_2") (pintype "passive"))
      (node (ref "C11") (pin "2") (pinfunction "2_2") (pintype "passive"))
      (node (ref "C14") (pin "2") (pinfunction "2_2") (pintype "passive"))
      (node (ref "C15") (pin "2") (pinfunction "2_2") (pintype "passive"))
      (node (ref "C16") (pin "2") (pinfunction "2_2") (pintype "passive"))
      (node (ref "C17") (pin "2") (pinfunction "2_2") (pintype "passive"))
      (node (ref "C18") (pin "2") (pinfunction "2_2") (pintype "passive"))
      (node (ref "C19") (pin "2") (pinfunction "2_2") (pintype "passive"))
      (node (ref "C2") (pin "2") (pinfunction "2_2") (pintype "passive"))
      (node (ref "C20") (pin "2") (pinfunction "2_2") (pintype "passive"))
      (node (ref "C3") (pin "2") (pinfunction "2_2") (pintype "passive"))
      (node (ref "C4") (pin "2") (pinfunction "2_2") (pintype "passive"))
      (node (ref "C5") (pin "2") (pinfunction "2_2") (pintype "passive"))
      (node (ref "C6") (pin "2") (pinfunction "2_2") (pintype "passive"))
      (node (ref "C7") (pin "2") (pinfunction "2_2") (pintype "passive"))
      (node (ref "C8") (pin "2") (pinfunction "2_2") (pintype "passive"))
      (node (ref "C9") (pin "2") (pinfunction "2_2") (pintype "passive"))
      (node (ref "D1") (pin "1") (pinfunction "A1_1") (pintype "passive"))
      (node (ref "D2") (pin "1") (pinfunction "A1_1") (pintype "passive"))
      (node (ref "D3") (pin "1") (pinfunction "A1_1") (pintype "passive"))
      (node (ref "D4") (pin "1") (pinfunction "A1_1") (pintype "passive"))
      (node (ref "D5") (pin "1") (pinfunction "A1_1") (pintype "passive"))
      (node (ref "D6") (pin "1") (pinfunction "A1_1") (pintype "passive"))
      (node (ref "IC1") (pin "11") (pinfunction "V-_11") (pintype "power_in"))
      (node (ref "IC2") (pin "14") (pinfunction "AGND_14") (pintype "bidirectional"))
      (node (ref "IC2") (pin "9") (pinfunction "DGND_9") (pintype "bidirectional"))
      (node (ref "IC3") (pin "10") (pinfunction "VSS_10") (pintype "power_in"))
      (node (ref "IC3") (pin "15") (pinfunction "A0_15") (pintype "input"))
      (node (ref "IC3") (pin "16") (pinfunction "A1_16") (pintype "input"))
      (node (ref "IC3") (pin "17") (pinfunction "A2_17") (pintype "input"))
      (node (ref "IC5") (pin "5") (pinfunction "A5_5") (pintype "passive"))
      (node (ref "IC6") (pin "3") (pinfunction "+IN_3") (pintype "input"))
      (node (ref "IC6") (pin "4") (pinfunction "V-_4") (pintype "power_in"))
      (node (ref "IC6") (pin "5") (pinfunction "+IN_5") (pintype "input"))
      (node (ref "IC7") (pin "5") (pinfunction "A5_5") (pintype "passive"))
      (node (ref "IC8") (pin "4") (pinfunction "V-_4") (pintype "power_in"))
      (node (ref "IC9") (pin "5") (pinfunction "GND_5") (pintype "power_in"))
      (node (ref "J1") (pin "14") (pinfunction "14_14") (pintype "passive"))
      (node (ref "J1") (pin "20") (pinfunction "20_20") (pintype "passive"))
      (node (ref "J1") (pin "25") (pinfunction "25_25") (pintype "passive"))
      (node (ref "J1") (pin "30") (pinfunction "30_30") (pintype "passive"))
      (node (ref "J1") (pin "39") (pinfunction "39_39") (pintype "passive"))
      (node (ref "J1") (pin "6") (pinfunction "6_6") (pintype "passive"))
      (node (ref "J1") (pin "9") (pinfunction "9_9") (pintype "passive"))
      (node (ref "J10") (pin "1") (pinfunction "1_1") (pintype "passive"))
      (node (ref "J15") (pin "1") (pinfunction "1_1") (pintype "passive"))
      (node (ref "J16") (pin "1") (pinfunction "1_1") (pintype "passive"))
      (node (ref "J2") (pin "1") (pinfunction "1_1") (pintype "passive"))
      (node (ref "J3") (pin "1") (pinfunction "1_1") (pintype "passive"))
      (node (ref "J4") (pin "1") (pinfunction "1_1") (pintype "passive"))
      (node (ref "J5") (pin "1") (pinfunction "1_1") (pintype "passive"))
      (node (ref "J8") (pin "1") (pinfunction "1_1") (pintype "passive"))
      (node (ref "OK1") (pin "12") (pinfunction "EMIT_12") (pintype "passive"))
      (node (ref "OK1") (pin "13") (pinfunction "EMIT_13") (pintype "passive"))
      (node (ref "OK1") (pin "16") (pinfunction "EMIT_16") (pintype "passive"))
      (node (ref "OK1") (pin "9") (pinfunction "EMIT_9") (pintype "passive"))
      (node (ref "OK2") (pin "12") (pinfunction "EMIT_12") (pintype "passive"))
      (node (ref "OK2") (pin "13") (pinfunction "EMIT_13") (pintype "passive"))
      (node (ref "OK2") (pin "16") (pinfunction "EMIT_16") (pintype "passive"))
      (node (ref "OK2") (pin "9") (pinfunction "EMIT_9") (pintype "passive"))
      (node (ref "OK3") (pin "12") (pinfunction "EMIT_12") (pintype "passive"))
      (node (ref "OK3") (pin "13") (pinfunction "EMIT_13") (pintype "passive"))
      (node (ref "OK3") (pin "16") (pinfunction "EMIT_16") (pintype "passive"))
      (node (ref "OK3") (pin "9") (pinfunction "EMIT_9") (pintype "passive"))
      (node (ref "R13") (pin "1") (pinfunction "1_1") (pintype "passive"))
      (node (ref "R14") (pin "1") (pinfunction "1_1") (pintype "passive"))
      (node (ref "R15") (pin "1") (pinfunction "1_1") (pintype "passive"))
      (node (ref "R16") (pin "1") (pinfunction "1_1") (pintype "passive"))
      (node (ref "R66") (pin "1") (pinfunction "1_1") (pintype "passive"))
      (node (ref "R70") (pin "1") (pinfunction "1_1") (pintype "passive"))
      (node (ref "R77") (pin "1") (pinfunction "1_1") (pintype "passive"))
      (node (ref "R79") (pin "1") (pinfunction "1_1") (pintype "passive"))
      (node (ref "S1") (pin "1") (pinfunction "1_1") (pintype "passive"))
    )
    (net (code "26") (name "GND-ISO") (class "Default")
      (node (ref "C12") (pin "2") (pinfunction "2_2") (pintype "passive"))
      (node (ref "C13") (pin "2") (pinfunction "2_2") (pintype "passive"))
      (node (ref "D7") (pin "1") (pinfunction "A1_1") (pintype "passive"))
      (node (ref "D8") (pin "1") (pinfunction "A1_1") (pintype "passive"))
      (node (ref "IC4") (pin "4") (pinfunction "V-_4") (pintype "power_in"))
      (node (ref "IC5") (pin "1") (pinfunction "C1_1") (pintype "passive"))
      (node (ref "IC7") (pin "1") (pinfunction "C1_1") (pintype "passive"))
      (node (ref "J7") (pin "4") (pinfunction "4_4") (pintype "bidirectional"))
      (node (ref "R18") (pin "1") (pinfunction "1_1") (pintype "passive"))
      (node (ref "R21") (pin "1") (pinfunction "1_1") (pintype "passive"))
      (node (ref "R24") (pin "1") (pinfunction "1_1") (pintype "passive"))
      (node (ref "R26") (pin "1") (pinfunction "1_1") (pintype "passive"))
      (node (ref "R30") (pin "1") (pinfunction "1_1") (pintype "passive"))
      (node (ref "R33") (pin "1") (pinfunction "1_1") (pintype "passive"))
      (node (ref "R36") (pin "1") (pinfunction "1_1") (pintype "passive"))
      (node (ref "R38") (pin "1") (pinfunction "1_1") (pintype "passive"))
      (node (ref "R42") (pin "1") (pinfunction "1_1") (pintype "passive"))
      (node (ref "R45") (pin "1") (pinfunction "1_1") (pintype "passive"))
      (node (ref "R48") (pin "1") (pinfunction "1_1") (pintype "passive"))
      (node (ref "R50") (pin "1") (pinfunction "1_1") (pintype "passive"))
      (node (ref "R53") (pin "1") (pinfunction "1_1") (pintype "passive"))
      (node (ref "R54") (pin "1") (pinfunction "1_1") (pintype "passive"))
      (node (ref "R59") (pin "1") (pinfunction "1_1") (pintype "passive"))
      (node (ref "R60") (pin "1") (pinfunction "1_1") (pintype "passive"))
      (node (ref "R72") (pin "1") (pinfunction "1_1") (pintype "passive"))
      (node (ref "R74") (pin "1") (pinfunction "1_1") (pintype "passive"))
    )
    (net (code "27") (name "GPIO6") (class "Default")
      (node (ref "J1") (pin "31") (pinfunction "31_31") (pintype "passive"))
      (node (ref "JP24") (pin "1") (pinfunction "1_1") (pintype "passive"))
    )
    (net (code "28") (name "GPIO13") (class "Default")
      (node (ref "J1") (pin "33") (pinfunction "33_33") (pintype "passive"))
      (node (ref "JP24") (pin "3") (pinfunction "3_3") (pintype "passive"))
    )
    (net (code "29") (name "GPIO17") (class "Default")
      (node (ref "J1") (pin "11") (pinfunction "11_11") (pintype "passive"))
    )
    (net (code "30") (name "GPIO19") (class "Default")
      (node (ref "J1") (pin "35") (pinfunction "35_35") (pintype "passive"))
      (node (ref "JP23") (pin "1") (pinfunction "1_1") (pintype "passive"))
    )
    (net (code "31") (name "GPIO22") (class "Default")
      (node (ref "J1") (pin "15") (pinfunction "15_15") (pintype "passive"))
    )
    (net (code "32") (name "GPIO26") (class "Default")
      (node (ref "J1") (pin "37") (pinfunction "37_37") (pintype "passive"))
      (node (ref "JP23") (pin "3") (pinfunction "3_3") (pintype "passive"))
    )
    (net (code "33") (name "GPIO27") (class "Default")
      (node (ref "J1") (pin "13") (pinfunction "13_13") (pintype "passive"))
    )
    (net (code "34") (name "HIGH_BEAM_P") (class "Default")
      (node (ref "J6") (pin "3") (pinfunction "3_3") (pintype "bidirectional"))
      (node (ref "JP3") (pin "2") (pinfunction "2_2") (pintype "passive"))
    )
    (net (code "35") (name "IN1N") (class "Default")
      (node (ref "JP1") (pin "3") (pinfunction "3_3") (pintype "passive"))
      (node (ref "OK1") (pin "2") (pinfunction "C_2") (pintype "passive"))
      (node (ref "R18") (pin "2") (pinfunction "2_2") (pintype "passive"))
    )
    (net (code "36") (name "IN1P") (class "Default")
      (node (ref "JP1") (pin "1") (pinfunction "1_1") (pintype "passive"))
      (node (ref "OK1") (pin "1") (pinfunction "A_1") (pintype "passive"))
      (node (ref "R17") (pin "1") (pinfunction "1_1") (pintype "passive"))
    )
    (net (code "37") (name "IN2N") (class "Default")
      (node (ref "JP2") (pin "3") (pinfunction "3_3") (pintype "passive"))
      (node (ref "OK1") (pin "3") (pinfunction "C_3") (pintype "passive"))
      (node (ref "R21") (pin "2") (pinfunction "2_2") (pintype "passive"))
    )
    (net (code "38") (name "IN2P") (class "Default")
      (node (ref "JP2") (pin "1") (pinfunction "1_1") (pintype "passive"))
      (node (ref "OK1") (pin "4") (pinfunction "A_4") (pintype "passive"))
      (node (ref "R20") (pin "1") (pinfunction "1_1") (pintype "passive"))
    )
    (net (code "39") (name "IN3N") (class "Default")
      (node (ref "JP3") (pin "3") (pinfunction "3_3") (pintype "passive"))
      (node (ref "OK1") (pin "6") (pinfunction "C_6") (pintype "passive"))
      (node (ref "R24") (pin "2") (pinfunction "2_2") (pintype "passive"))
    )
    (net (code "40") (name "IN3P") (class "Default")
      (node (ref "JP3") (pin "1") (pinfunction "1_1") (pintype "passive"))
      (node (ref "OK1") (pin "5") (pinfunction "A_5") (pintype "passive"))
      (node (ref "R23") (pin "1") (pinfunction "1_1") (pintype "passive"))
    )
    (net (code "41") (name "IN4N") (class "Default")
      (node (ref "JP4") (pin "3") (pinfunction "3_3") (pintype "passive"))
      (node (ref "OK1") (pin "7") (pinfunction "C_7") (pintype "passive"))
      (node (ref "R26") (pin "2") (pinfunction "2_2") (pintype "passive"))
    )
    (net (code "42") (name "IN4P") (class "Default")
      (node (ref "JP4") (pin "1") (pinfunction "1_1") (pintype "passive"))
      (node (ref "OK1") (pin "8") (pinfunction "A_8") (pintype "passive"))
      (node (ref "R25") (pin "1") (pinfunction "1_1") (pintype "passive"))
    )
    (net (code "43") (name "IN5N") (class "Default")
      (node (ref "JP5") (pin "3") (pinfunction "3_3") (pintype "passive"))
      (node (ref "OK2") (pin "2") (pinfunction "C_2") (pintype "passive"))
      (node (ref "R30") (pin "2") (pinfunction "2_2") (pintype "passive"))
    )
    (net (code "44") (name "IN5P") (class "Default")
      (node (ref "JP5") (pin "1") (pinfunction "1_1") (pintype "passive"))
      (node (ref "OK2") (pin "1") (pinfunction "A_1") (pintype "passive"))
      (node (ref "R29") (pin "1") (pinfunction "1_1") (pintype "passive"))
    )
    (net (code "45") (name "IN6N") (class "Default")
      (node (ref "JP6") (pin "3") (pinfunction "3_3") (pintype "passive"))
      (node (ref "OK2") (pin "3") (pinfunction "C_3") (pintype "passive"))
      (node (ref "R33") (pin "2") (pinfunction "2_2") (pintype "passive"))
    )
    (net (code "46") (name "IN6P") (class "Default")
      (node (ref "JP6") (pin "1") (pinfunction "1_1") (pintype "passive"))
      (node (ref "OK2") (pin "4") (pinfunction "A_4") (pintype "passive"))
      (node (ref "R32") (pin "1") (pinfunction "1_1") (pintype "passive"))
    )
    (net (code "47") (name "IN7N") (class "Default")
      (node (ref "JP7") (pin "3") (pinfunction "3_3") (pintype "passive"))
      (node (ref "OK2") (pin "6") (pinfunction "C_6") (pintype "passive"))
      (node (ref "R36") (pin "2") (pinfunction "2_2") (pintype "passive"))
    )
    (net (code "48") (name "IN7P") (class "Default")
      (node (ref "JP7") (pin "1") (pinfunction "1_1") (pintype "passive"))
      (node (ref "OK2") (pin "5") (pinfunction "A_5") (pintype "passive"))
      (node (ref "R35") (pin "1") (pinfunction "1_1") (pintype "passive"))
    )
    (net (code "49") (name "IN8N") (class "Default")
      (node (ref "JP8") (pin "3") (pinfunction "3_3") (pintype "passive"))
      (node (ref "OK2") (pin "7") (pinfunction "C_7") (pintype "passive"))
      (node (ref "R38") (pin "2") (pinfunction "2_2") (pintype "passive"))
    )
    (net (code "50") (name "IN8P") (class "Default")
      (node (ref "JP8") (pin "1") (pinfunction "1_1") (pintype "passive"))
      (node (ref "OK2") (pin "8") (pinfunction "A_8") (pintype "passive"))
      (node (ref "R37") (pin "1") (pinfunction "1_1") (pintype "passive"))
    )
    (net (code "51") (name "IN9N") (class "Default")
      (node (ref "JP9") (pin "3") (pinfunction "3_3") (pintype "passive"))
      (node (ref "OK3") (pin "2") (pinfunction "C_2") (pintype "passive"))
      (node (ref "R42") (pin "2") (pinfunction "2_2") (pintype "passive"))
    )
    (net (code "52") (name "IN9P") (class "Default")
      (node (ref "JP9") (pin "1") (pinfunction "1_1") (pintype "passive"))
      (node (ref "OK3") (pin "1") (pinfunction "A_1") (pintype "passive"))
      (node (ref "R41") (pin "1") (pinfunction "1_1") (pintype "passive"))
    )
    (net (code "53") (name "IN10N") (class "Default")
      (node (ref "JP10") (pin "3") (pinfunction "3_3") (pintype "passive"))
      (node (ref "OK3") (pin "3") (pinfunction "C_3") (pintype "passive"))
      (node (ref "R45") (pin "2") (pinfunction "2_2") (pintype "passive"))
    )
    (net (code "54") (name "IN10P") (class "Default")
      (node (ref "JP10") (pin "1") (pinfunction "1_1") (pintype "passive"))
      (node (ref "OK3") (pin "4") (pinfunction "A_4") (pintype "passive"))
      (node (ref "R44") (pin "1") (pinfunction "1_1") (pintype "passive"))
    )
    (net (code "55") (name "IN11N") (class "Default")
      (node (ref "JP11") (pin "3") (pinfunction "3_3") (pintype "passive"))
      (node (ref "OK3") (pin "6") (pinfunction "C_6") (pintype "passive"))
      (node (ref "R48") (pin "2") (pinfunction "2_2") (pintype "passive"))
    )
    (net (code "56") (name "IN11P") (class "Default")
      (node (ref "JP11") (pin "1") (pinfunction "1_1") (pintype "passive"))
      (node (ref "OK3") (pin "5") (pinfunction "A_5") (pintype "passive"))
      (node (ref "R47") (pin "1") (pinfunction "1_1") (pintype "passive"))
    )
    (net (code "57") (name "IN12N") (class "Default")
      (node (ref "JP12") (pin "3") (pinfunction "3_3") (pintype "passive"))
      (node (ref "OK3") (pin "7") (pinfunction "C_7") (pintype "passive"))
      (node (ref "R50") (pin "2") (pinfunction "2_2") (pintype "passive"))
    )
    (net (code "58") (name "IN12P") (class "Default")
      (node (ref "JP12") (pin "1") (pinfunction "1_1") (pintype "passive"))
      (node (ref "OK3") (pin "8") (pinfunction "A_8") (pintype "passive"))
      (node (ref "R49") (pin "1") (pinfunction "1_1") (pintype "passive"))
    )
    (net (code "59") (name "MAP_SENSOR") (class "Default")
      (node (ref "JP19") (pin "3") (pinfunction "3_3") (pintype "passive"))
    )
    (net (code "60") (name "Net-(BT1-+)") (class "Default")
      (node (ref "BT1") (pin "PWR@1") (pinfunction "+_PWR@1") (pintype "power_in"))
      (node (ref "IC9") (pin "3") (pinfunction "VBKP_3") (pintype "power_in"))
    )
    (net (code "61") (name "Net-(D1-C1A2)") (class "Default")
      (node (ref "D1") (pin "3") (pinfunction "C1A2_3") (pintype "passive"))
      (node (ref "IC1") (pin "3") (pinfunction "+IN_3") (pintype "input"))
      (node (ref "R1") (pin "2") (pinfunction "2_2") (pintype "passive"))
    )
    (net (code "62") (name "Net-(D2-C1A2)") (class "Default")
      (node (ref "D2") (pin "3") (pinfunction "C1A2_3") (pintype "passive"))
      (node (ref "IC1") (pin "5") (pinfunction "+IN_5") (pintype "input"))
      (node (ref "R4") (pin "2") (pinfunction "2_2") (pintype "passive"))
    )
    (net (code "63") (name "Net-(D3-C1A2)") (class "Default")
      (node (ref "D3") (pin "3") (pinfunction "C1A2_3") (pintype "passive"))
      (node (ref "IC1") (pin "10") (pinfunction "+IN_10") (pintype "input"))
      (node (ref "R6") (pin "2") (pinfunction "2_2") (pintype "passive"))
    )
    (net (code "64") (name "Net-(D4-C1A2)") (class "Default")
      (node (ref "D4") (pin "3") (pinfunction "C1A2_3") (pintype "passive"))
      (node (ref "IC1") (pin "12") (pinfunction "+IN_12") (pintype "input"))
      (node (ref "R8") (pin "2") (pinfunction "2_2") (pintype "passive"))
    )
    (net (code "65") (name "Net-(D5-C1A2)") (class "Default")
      (node (ref "D5") (pin "3") (pinfunction "C1A2_3") (pintype "passive"))
      (node (ref "IC8") (pin "3") (pinfunction "+IN_3") (pintype "input"))
      (node (ref "R65") (pin "2") (pinfunction "2_2") (pintype "passive"))
    )
    (net (code "66") (name "Net-(D6-C1A2)") (class "Default")
      (node (ref "D6") (pin "3") (pinfunction "C1A2_3") (pintype "passive"))
      (node (ref "IC8") (pin "5") (pinfunction "+IN_5") (pintype "input"))
      (node (ref "R69") (pin "2") (pinfunction "2_2") (pintype "passive"))
    )
    (net (code "67") (name "Net-(D7-C1A2)") (class "Default")
      (node (ref "D7") (pin "3") (pinfunction "C1A2_3") (pintype "passive"))
      (node (ref "IC4") (pin "3") (pinfunction "+IN_3") (pintype "input"))
      (node (ref "R57") (pin "2") (pinfunction "2_2") (pintype "passive"))
    )
    (net (code "68") (name "Net-(D8-C1A2)") (class "Default")
      (node (ref "D8") (pin "3") (pinfunction "C1A2_3") (pintype "passive"))
      (node (ref "IC4") (pin "5") (pinfunction "+IN_5") (pintype "input"))
      (node (ref "R58") (pin "2") (pinfunction "2_2") (pintype "passive"))
    )
    (net (code "69") (name "Net-(IC1A--IN)") (class "Default")
      (node (ref "IC1") (pin "1") (pinfunction "OUT_1") (pintype "output"))
      (node (ref "IC1") (pin "2") (pinfunction "-IN_2") (pintype "input"))
      (node (ref "R2") (pin "2") (pinfunction "2_2") (pintype "passive"))
    )
    (net (code "70") (name "Net-(IC1B--IN)") (class "Default")
      (node (ref "IC1") (pin "6") (pinfunction "-IN_6") (pintype "input"))
      (node (ref "IC1") (pin "7") (pinfunction "OUT_7") (pintype "output"))
      (node (ref "R3") (pin "2") (pinfunction "2_2") (pintype "passive"))
    )
    (net (code "71") (name "Net-(IC1C--IN)") (class "Default")
      (node (ref "IC1") (pin "8") (pinfunction "OUT_8") (pintype "output"))
      (node (ref "IC1") (pin "9") (pinfunction "-IN_9") (pintype "input"))
      (node (ref "R5") (pin "2") (pinfunction "2_2") (pintype "passive"))
    )
    (net (code "72") (name "Net-(IC1D--IN)") (class "Default")
      (node (ref "IC1") (pin "13") (pinfunction "-IN_13") (pintype "input"))
      (node (ref "IC1") (pin "14") (pinfunction "OUT_14") (pintype "output"))
      (node (ref "R7") (pin "2") (pinfunction "2_2") (pintype "passive"))
    )
    (net (code "73") (name "Net-(IC4A--IN)") (class "Default")
      (node (ref "IC4") (pin "2") (pinfunction "-IN_2") (pintype "input"))
      (node (ref "IC5") (pin "4") (pinfunction "A4_4") (pintype "passive"))
      (node (ref "R53") (pin "2") (pinfunction "2_2") (pintype "passive"))
      (node (ref "R54") (pin "2") (pinfunction "2_2") (pintype "passive"))
    )
    (net (code "74") (name "Net-(IC4A-OUT)") (class "Default")
      (node (ref "IC4") (pin "1") (pinfunction "OUT_1") (pintype "output"))
      (node (ref "R55") (pin "1") (pinfunction "1_1") (pintype "passive"))
    )
    (net (code "75") (name "Net-(IC4B--IN)") (class "Default")
      (node (ref "IC4") (pin "6") (pinfunction "-IN_6") (pintype "input"))
      (node (ref "IC7") (pin "4") (pinfunction "A4_4") (pintype "passive"))
      (node (ref "R59") (pin "2") (pinfunction "2_2") (pintype "passive"))
      (node (ref "R60") (pin "2") (pinfunction "2_2") (pintype "passive"))
    )
    (net (code "76") (name "Net-(IC4B-OUT)") (class "Default")
      (node (ref "IC4") (pin "7") (pinfunction "OUT_7") (pintype "output"))
      (node (ref "R61") (pin "1") (pinfunction "1_1") (pintype "passive"))
    )
    (net (code "77") (name "Net-(IC5-A2)") (class "Default")
      (node (ref "IC5") (pin "2") (pinfunction "A2_2") (pintype "passive"))
      (node (ref "R55") (pin "2") (pinfunction "2_2") (pintype "passive"))
    )
    (net (code "78") (name "Net-(IC5-C6)") (class "Default")
      (node (ref "IC5") (pin "6") (pinfunction "C6_6") (pintype "passive"))
      (node (ref "IC6") (pin "2") (pinfunction "-IN_2") (pintype "input"))
      (node (ref "R56") (pin "1") (pinfunction "1_1") (pintype "passive"))
    )
    (net (code "79") (name "Net-(IC6B--IN)") (class "Default")
      (node (ref "IC6") (pin "6") (pinfunction "-IN_6") (pintype "input"))
      (node (ref "IC7") (pin "6") (pinfunction "C6_6") (pintype "passive"))
      (node (ref "R62") (pin "1") (pinfunction "1_1") (pintype "passive"))
    )
    (net (code "80") (name "Net-(IC7-A2)") (class "Default")
      (node (ref "IC7") (pin "2") (pinfunction "A2_2") (pintype "passive"))
      (node (ref "R61") (pin "2") (pinfunction "2_2") (pintype "passive"))
    )
    (net (code "81") (name "Net-(IC8A--IN)") (class "Default")
      (node (ref "IC8") (pin "1") (pinfunction "OUT_1") (pintype "output"))
      (node (ref "IC8") (pin "2") (pinfunction "-IN_2") (pintype "input"))
      (node (ref "R64") (pin "2") (pinfunction "2_2") (pintype "passive"))
    )
    (net (code "82") (name "Net-(IC8B--IN)") (class "Default")
      (node (ref "IC8") (pin "6") (pinfunction "-IN_6") (pintype "input"))
      (node (ref "IC8") (pin "7") (pinfunction "OUT_7") (pintype "output"))
      (node (ref "R68") (pin "2") (pinfunction "2_2") (pintype "passive"))
    )
    (net (code "83") (name "Net-(IC9-SQW)") (class "Default")
      (node (ref "IC9") (pin "9") (pinfunction "SQW_9") (pintype "output"))
      (node (ref "R75") (pin "1") (pinfunction "1_1") (pintype "passive"))
    )
    (net (code "84") (name "Net-(IC9-X1)") (class "Default")
      (node (ref "IC9") (pin "1") (pinfunction "X1_1") (pintype "bidirectional"))
      (node (ref "Y1") (pin "2") (pinfunction "2_2") (pintype "passive"))
    )
    (net (code "85") (name "Net-(IC9-X2)") (class "Default")
      (node (ref "IC9") (pin "2") (pinfunction "X2_2") (pintype "bidirectional"))
      (node (ref "Y1") (pin "1") (pinfunction "1_1") (pintype "passive"))
    )
    (net (code "86") (name "Net-(IC9-~{RST})") (class "Default")
      (node (ref "IC9") (pin "4") (pinfunction "~{RST}_4") (pintype "input"))
      (node (ref "S1") (pin "2") (pinfunction "2_2") (pintype "passive"))
    )
    (net (code "87") (name "Net-(J11-Pad1)") (class "Default")
      (node (ref "J11") (pin "1") (pinfunction "1_1") (pintype "passive"))
      (node (ref "J9") (pin "1") (pinfunction "1_1") (pintype "passive"))
      (node (ref "JP21") (pin "3") (pinfunction "3_3") (pintype "passive"))
    )
    (net (code "88") (name "Net-(J11-Pad2)") (class "Default")
      (node (ref "J11") (pin "2") (pinfunction "2_2") (pintype "passive"))
      (node (ref "J9") (pin "2") (pinfunction "2_2") (pintype "passive"))
    )
    (net (code "89") (name "Net-(J11-Pad3)") (class "Default")
      (node (ref "J11") (pin "3") (pinfunction "3_3") (pintype "passive"))
      (node (ref "J9") (pin "3") (pinfunction "3_3") (pintype "passive"))
      (node (ref "JP21") (pin "1") (pinfunction "1_1") (pintype "passive"))
    )
    (net (code "90") (name "Net-(J15-Pad2)") (class "Default")
      (node (ref "J15") (pin "2") (pinfunction "2_2") (pintype "passive"))
      (node (ref "JP23") (pin "2") (pinfunction "2_2") (pintype "passive"))
      (node (ref "R78") (pin "1") (pinfunction "1_1") (pintype "passive"))
      (node (ref "R79") (pin "2") (pinfunction "2_2") (pintype "passive"))
    )
    (net (code "91") (name "Net-(J16-Pad2)") (class "Default")
      (node (ref "J16") (pin "2") (pinfunction "2_2") (pintype "passive"))
      (node (ref "JP24") (pin "2") (pinfunction "2_2") (pintype "passive"))
      (node (ref "R76") (pin "1") (pinfunction "1_1") (pintype "passive"))
      (node (ref "R77") (pin "2") (pinfunction "2_2") (pintype "passive"))
    )
    (net (code "92") (name "Net-(JP13-Pad2)") (class "Default")
      (node (ref "JP13") (pin "2") (pinfunction "2_2") (pintype "passive"))
      (node (ref "R1") (pin "1") (pinfunction "1_1") (pintype "passive"))
      (node (ref "R9") (pin "1") (pinfunction "1_1") (pintype "passive"))
    )
    (net (code "93") (name "Net-(JP14-Pad2)") (class "Default")
      (node (ref "JP14") (pin "2") (pinfunction "2_2") (pintype "passive"))
      (node (ref "R10") (pin "1") (pinfunction "1_1") (pintype "passive"))
      (node (ref "R4") (pin "1") (pinfunction "1_1") (pintype "passive"))
    )
    (net (code "94") (name "Net-(JP15-Pad2)") (class "Default")
      (node (ref "JP15") (pin "2") (pinfunction "2_2") (pintype "passive"))
      (node (ref "R11") (pin "1") (pinfunction "1_1") (pintype "passive"))
      (node (ref "R6") (pin "1") (pinfunction "1_1") (pintype "passive"))
    )
    (net (code "95") (name "Net-(JP16-Pad2)") (class "Default")
      (node (ref "JP16") (pin "2") (pinfunction "2_2") (pintype "passive"))
      (node (ref "R12") (pin "1") (pinfunction "1_1") (pintype "passive"))
      (node (ref "R8") (pin "1") (pinfunction "1_1") (pintype "passive"))
    )
    (net (code "96") (name "Net-(JP17-Pad2)") (class "Default")
      (node (ref "JP17") (pin "2") (pinfunction "2_2") (pintype "passive"))
      (node (ref "R73") (pin "1") (pinfunction "1_1") (pintype "passive"))
    )
    (net (code "97") (name "Net-(JP18-Pad2)") (class "Default")
      (node (ref "JP18") (pin "2") (pinfunction "2_2") (pintype "passive"))
      (node (ref "R71") (pin "1") (pinfunction "1_1") (pintype "passive"))
    )
    (net (code "98") (name "Net-(JP19-Pad2)") (class "Default")
      (node (ref "JP19") (pin "2") (pinfunction "2_2") (pintype "passive"))
      (node (ref "R63") (pin "1") (pinfunction "1_1") (pintype "passive"))
      (node (ref "R65") (pin "1") (pinfunction "1_1") (pintype "passive"))
    )
    (net (code "99") (name "Net-(JP20-Pad2)") (class "Default")
      (node (ref "JP20") (pin "2") (pinfunction "2_2") (pintype "passive"))
      (node (ref "R67") (pin "1") (pinfunction "1_1") (pintype "passive"))
      (node (ref "R69") (pin "1") (pinfunction "1_1") (pintype "passive"))
    )
    (net (code "100") (name "Net-(R57-Pad1)") (class "Default")
      (node (ref "R57") (pin "1") (pinfunction "1_1") (pintype "passive"))
      (node (ref "R73") (pin "2") (pinfunction "2_2") (pintype "passive"))
      (node (ref "R74") (pin "2") (pinfunction "2_2") (pintype "passive"))
    )
    (net (code "101") (name "Net-(R58-Pad1)") (class "Default")
      (node (ref "R58") (pin "1") (pinfunction "1_1") (pintype "passive"))
      (node (ref "R71") (pin "2") (pinfunction "2_2") (pintype "passive"))
      (node (ref "R72") (pin "2") (pinfunction "2_2") (pintype "passive"))
    )
    (net (code "102") (name "OD_LAMP_AUTO_P") (class "Default")
      (node (ref "J13") (pin "1") (pinfunction "1_1") (pintype "passive"))
      (node (ref "JP9") (pin "2") (pinfunction "2_2") (pintype "passive"))
    )
    (net (code "103") (name "OD_LAMP_P") (class "Default")
      (node (ref "J6") (pin "4") (pinfunction "4_4") (pintype "bidirectional"))
      (node (ref "JP2") (pin "2") (pinfunction "2_2") (pintype "passive"))
    )
    (net (code "104") (name "OIL_PRESSURE") (class "Default")
      (node (ref "JP15") (pin "3") (pinfunction "3_3") (pintype "passive"))
    )
    (net (code "105") (name "OIL_PRESS_SW_N") (class "Default")
      (node (ref "J6") (pin "5") (pinfunction "5_5") (pintype "bidirectional"))
      (node (ref "JP1") (pin "2") (pinfunction "2_2") (pintype "passive"))
    )
    (net (code "106") (name "OIL_TEMP") (class "Default")
      (node (ref "JP16") (pin "3") (pinfunction "3_3") (pintype "passive"))
    )
    (net (code "107") (name "OUT1") (class "Default")
      (node (ref "IC3") (pin "21") (pinfunction "GPA0_21") (pintype "bidirectional"))
      (node (ref "OK1") (pin "15") (pinfunction "COL_15") (pintype "passive"))
      (node (ref "R19") (pin "1") (pinfunction "1_1") (pintype "passive"))
    )
    (net (code "108") (name "OUT2") (class "Default")
      (node (ref "IC3") (pin "22") (pinfunction "GPA1_22") (pintype "bidirectional"))
      (node (ref "OK1") (pin "14") (pinfunction "COL_14") (pintype "passive"))
      (node (ref "R22") (pin "1") (pinfunction "1_1") (pintype "passive"))
    )
    (net (code "109") (name "OUT3") (class "Default")
      (node (ref "IC3") (pin "23") (pinfunction "GPA2_23") (pintype "bidirectional"))
      (node (ref "OK1") (pin "11") (pinfunction "COL_11") (pintype "passive"))
      (node (ref "R27") (pin "1") (pinfunction "1_1") (pintype "passive"))
    )
    (net (code "110") (name "OUT4") (class "Default")
      (node (ref "IC3") (pin "24") (pinfunction "GPA3_24") (pintype "bidirectional"))
      (node (ref "OK1") (pin "10") (pinfunction "COL_10") (pintype "passive"))
      (node (ref "R28") (pin "1") (pinfunction "1_1") (pintype "passive"))
    )
    (net (code "111") (name "OUT5") (class "Default")
      (node (ref "IC3") (pin "28") (pinfunction "GPA7_28") (pintype "bidirectional"))
      (node (ref "OK2") (pin "15") (pinfunction "COL_15") (pintype "passive"))
      (node (ref "R31") (pin "1") (pinfunction "1_1") (pintype "passive"))
    )
    (net (code "112") (name "OUT6") (class "Default")
      (node (ref "IC3") (pin "27") (pinfunction "GPA6_27") (pintype "bidirectional"))
      (node (ref "OK2") (pin "14") (pinfunction "COL_14") (pintype "passive"))
      (node (ref "R34") (pin "1") (pinfunction "1_1") (pintype "passive"))
    )
    (net (code "113") (name "OUT7") (class "Default")
      (node (ref "IC3") (pin "26") (pinfunction "GPA5_26") (pintype "bidirectional"))
      (node (ref "OK2") (pin "11") (pinfunction "COL_11") (pintype "passive"))
      (node (ref "R39") (pin "1") (pinfunction "1_1") (pintype "passive"))
    )
    (net (code "114") (name "OUT8") (class "Default")
      (node (ref "IC3") (pin "25") (pinfunction "GPA4_25") (pintype "bidirectional"))
      (node (ref "OK2") (pin "10") (pinfunction "COL_10") (pintype "passive"))
      (node (ref "R40") (pin "1") (pinfunction "1_1") (pintype "passive"))
    )
    (net (code "115") (name "OUT9") (class "Default")
      (node (ref "IC3") (pin "1") (pinfunction "GPB0_1") (pintype "bidirectional"))
      (node (ref "OK3") (pin "15") (pinfunction "COL_15") (pintype "passive"))
      (node (ref "R43") (pin "1") (pinfunction "1_1") (pintype "passive"))
    )
    (net (code "116") (name "OUT10") (class "Default")
      (node (ref "IC3") (pin "2") (pinfunction "GPB1_2") (pintype "bidirectional"))
      (node (ref "OK3") (pin "14") (pinfunction "COL_14") (pintype "passive"))
      (node (ref "R46") (pin "1") (pinfunction "1_1") (pintype "passive"))
    )
    (net (code "117") (name "OUT11") (class "Default")
      (node (ref "IC3") (pin "3") (pinfunction "GPB2_3") (pintype "bidirectional"))
      (node (ref "OK3") (pin "11") (pinfunction "COL_11") (pintype "passive"))
      (node (ref "R51") (pin "1") (pinfunction "1_1") (pintype "passive"))
    )
    (net (code "118") (name "OUT12") (class "Default")
      (node (ref "IC3") (pin "4") (pinfunction "GPB3_4") (pintype "bidirectional"))
      (node (ref "OK3") (pin "10") (pinfunction "COL_10") (pintype "passive"))
      (node (ref "R52") (pin "1") (pinfunction "1_1") (pintype "passive"))
    )
    (net (code "119") (name "PARKING_BRAKE_N") (class "Default")
      (node (ref "J7") (pin "2") (pinfunction "2_2") (pintype "bidirectional"))
      (node (ref "JP11") (pin "2") (pinfunction "2_2") (pintype "passive"))
    )
    (net (code "120") (name "SCL") (class "Default")
      (node (ref "IC3") (pin "12") (pinfunction "SCL_12") (pintype "input"))
      (node (ref "IC9") (pin "7") (pinfunction "SCL_7") (pintype "bidirectional"))
      (node (ref "J1") (pin "5") (pinfunction "5_5") (pintype "passive"))
    )
    (net (code "121") (name "SDA") (class "Default")
      (node (ref "IC3") (pin "13") (pinfunction "SDA_13") (pintype "bidirectional"))
      (node (ref "IC9") (pin "6") (pinfunction "SDA_6") (pintype "bidirectional"))
      (node (ref "J1") (pin "3") (pinfunction "3_3") (pintype "passive"))
    )
    (net (code "122") (name "SENSOR1_IN") (class "Default")
      (node (ref "J2") (pin "2") (pinfunction "2_2") (pintype "passive"))
      (node (ref "JP13") (pin "1") (pinfunction "1_1") (pintype "passive"))
    )
    (net (code "123") (name "SENSOR2_IN") (class "Default")
      (node (ref "J3") (pin "2") (pinfunction "2_2") (pintype "passive"))
      (node (ref "JP14") (pin "1") (pinfunction "1_1") (pintype "passive"))
    )
    (net (code "124") (name "SENSOR3_IN") (class "Default")
      (node (ref "J4") (pin "2") (pinfunction "2_2") (pintype "passive"))
      (node (ref "JP15") (pin "1") (pinfunction "1_1") (pintype "passive"))
    )
    (net (code "125") (name "SENSOR4_IN") (class "Default")
      (node (ref "J5") (pin "2") (pinfunction "2_2") (pintype "passive"))
      (node (ref "JP16") (pin "1") (pinfunction "1_1") (pintype "passive"))
    )
    (net (code "126") (name "SENSOR5_IN") (class "Default")
      (node (ref "J10") (pin "2") (pinfunction "2_2") (pintype "passive"))
      (node (ref "JP19") (pin "1") (pinfunction "1_1") (pintype "passive"))
    )
    (net (code "127") (name "SENSOR6_IN") (class "Default")
      (node (ref "J8") (pin "2") (pinfunction "2_2") (pintype "passive"))
      (node (ref "JP20") (pin "1") (pinfunction "1_1") (pintype "passive"))
    )
    (net (code "128") (name "SIG_3V3_IN1") (class "Default")
      (node (ref "IC2") (pin "7") (pinfunction "CH6_7") (pintype "bidirectional"))
      (node (ref "IC6") (pin "1") (pinfunction "OUT_1") (pintype "output"))
      (node (ref "R56") (pin "2") (pinfunction "2_2") (pintype "passive"))
    )
    (net (code "129") (name "SIG_3V3_IN2") (class "Default")
      (node (ref "IC2") (pin "8") (pinfunction "CH7_8") (pintype "bidirectional"))
      (node (ref "IC6") (pin "7") (pinfunction "OUT_7") (pintype "output"))
      (node (ref "R62") (pin "2") (pinfunction "2_2") (pintype "passive"))
    )
    (net (code "130") (name "SIG_12V_IN1") (class "Default")
      (node (ref "JP17") (pin "1") (pinfunction "1_1") (pintype "passive"))
    )
    (net (code "131") (name "SIG_12V_IN2") (class "Default")
      (node (ref "JP18") (pin "1") (pinfunction "1_1") (pintype "passive"))
    )
    (net (code "132") (name "SPI_CE0_N") (class "Default")
      (node (ref "J1") (pin "24") (pinfunction "24_24") (pintype "passive"))
      (node (ref "JP22") (pin "3") (pinfunction "3_3") (pintype "passive"))
    )
    (net (code "133") (name "SPI_CE1_N") (class "Default")
      (node (ref "J1") (pin "26") (pinfunction "26_26") (pintype "passive"))
      (node (ref "JP22") (pin "1") (pinfunction "1_1") (pintype "passive"))
    )
    (net (code "134") (name "SPI_CLK") (class "Default")
      (node (ref "IC2") (pin "13") (pinfunction "CLK_13") (pintype "bidirectional"))
      (node (ref "J1") (pin "23") (pinfunction "23_23") (pintype "passive"))
    )
    (net (code "135") (name "SPI_MISO") (class "Default")
      (node (ref "IC2") (pin "12") (pinfunction "DOUT_12") (pintype "bidirectional"))
      (node (ref "J1") (pin "21") (pinfunction "21_21") (pintype "passive"))
    )
    (net (code "136") (name "SPI_MOSI") (class "Default")
      (node (ref "IC2") (pin "11") (pinfunction "DIN_11") (pintype "bidirectional"))
      (node (ref "J1") (pin "19") (pinfunction "19_19") (pintype "passive"))
    )
    (net (code "137") (name "unconnected-(IC3-GPB4-Pad5)") (class "Default")
      (node (ref "IC3") (pin "5") (pinfunction "GPB4_5") (pintype "bidirectional"))
    )
    (net (code "138") (name "unconnected-(IC3-GPB5-Pad6)") (class "Default")
      (node (ref "IC3") (pin "6") (pinfunction "GPB5_6") (pintype "bidirectional"))
    )
    (net (code "139") (name "unconnected-(IC3-GPB6-Pad7)") (class "Default")
      (node (ref "IC3") (pin "7") (pinfunction "GPB6_7") (pintype "bidirectional"))
    )
    (net (code "140") (name "unconnected-(IC3-GPB7-Pad8)") (class "Default")
      (node (ref "IC3") (pin "8") (pinfunction "GPB7_8") (pintype "bidirectional"))
    )
    (net (code "141") (name "unconnected-(IC3-INTA-Pad20)") (class "Default")
      (node (ref "IC3") (pin "20") (pinfunction "INTA_20") (pintype "output"))
    )
    (net (code "142") (name "unconnected-(IC3-INTB-Pad19)") (class "Default")
      (node (ref "IC3") (pin "19") (pinfunction "INTB_19") (pintype "output"))
    )
    (net (code "143") (name "unconnected-(IC9-~{INT}-Pad8)") (class "Default")
      (node (ref "IC9") (pin "8") (pinfunction "~{INT}_8") (pintype "output"))
    )
    (net (code "144") (name "unconnected-(J1-Pad7)") (class "Default")
      (node (ref "J1") (pin "7") (pinfunction "7_7") (pintype "passive"))
    )
    (net (code "145") (name "unconnected-(J1-Pad8)") (class "Default")
      (node (ref "J1") (pin "8") (pinfunction "8_8") (pintype "passive"))
    )
    (net (code "146") (name "unconnected-(J1-Pad10)") (class "Default")
      (node (ref "J1") (pin "10") (pinfunction "10_10") (pintype "passive"))
    )
    (net (code "147") (name "unconnected-(J1-Pad12)") (class "Default")
      (node (ref "J1") (pin "12") (pinfunction "12_12") (pintype "passive"))
    )
    (net (code "148") (name "unconnected-(J1-Pad16)") (class "Default")
      (node (ref "J1") (pin "16") (pinfunction "16_16") (pintype "passive"))
    )
    (net (code "149") (name "unconnected-(J1-Pad18)") (class "Default")
      (node (ref "J1") (pin "18") (pinfunction "18_18") (pintype "passive"))
    )
    (net (code "150") (name "unconnected-(J1-Pad22)") (class "Default")
      (node (ref "J1") (pin "22") (pinfunction "22_22") (pintype "passive"))
    )
    (net (code "151") (name "unconnected-(J1-Pad27)") (class "Default")
      (node (ref "J1") (pin "27") (pinfunction "27_27") (pintype "passive"))
    )
    (net (code "152") (name "unconnected-(J1-Pad28)") (class "Default")
      (node (ref "J1") (pin "28") (pinfunction "28_28") (pintype "passive"))
    )
    (net (code "153") (name "unconnected-(J1-Pad29)") (class "Default")
      (node (ref "J1") (pin "29") (pinfunction "29_29") (pintype "passive"))
    )
    (net (code "154") (name "unconnected-(J1-Pad32)") (class "Default")
      (node (ref "J1") (pin "32") (pinfunction "32_32") (pintype "passive"))
    )
    (net (code "155") (name "unconnected-(J1-Pad34)") (class "Default")
      (node (ref "J1") (pin "34") (pinfunction "34_34") (pintype "passive"))
    )
    (net (code "156") (name "unconnected-(J1-Pad36)") (class "Default")
      (node (ref "J1") (pin "36") (pinfunction "36_36") (pintype "passive"))
    )
    (net (code "157") (name "unconnected-(J1-Pad38)") (class "Default")
      (node (ref "J1") (pin "38") (pinfunction "38_38") (pintype "passive"))
    )
    (net (code "158") (name "unconnected-(J1-Pad40)") (class "Default")
      (node (ref "J1") (pin "40") (pinfunction "40_40") (pintype "passive"))
    )
  )
)
